# TSB_Rev1.net
KiCad netlist of a schematic drawn in EAGLE
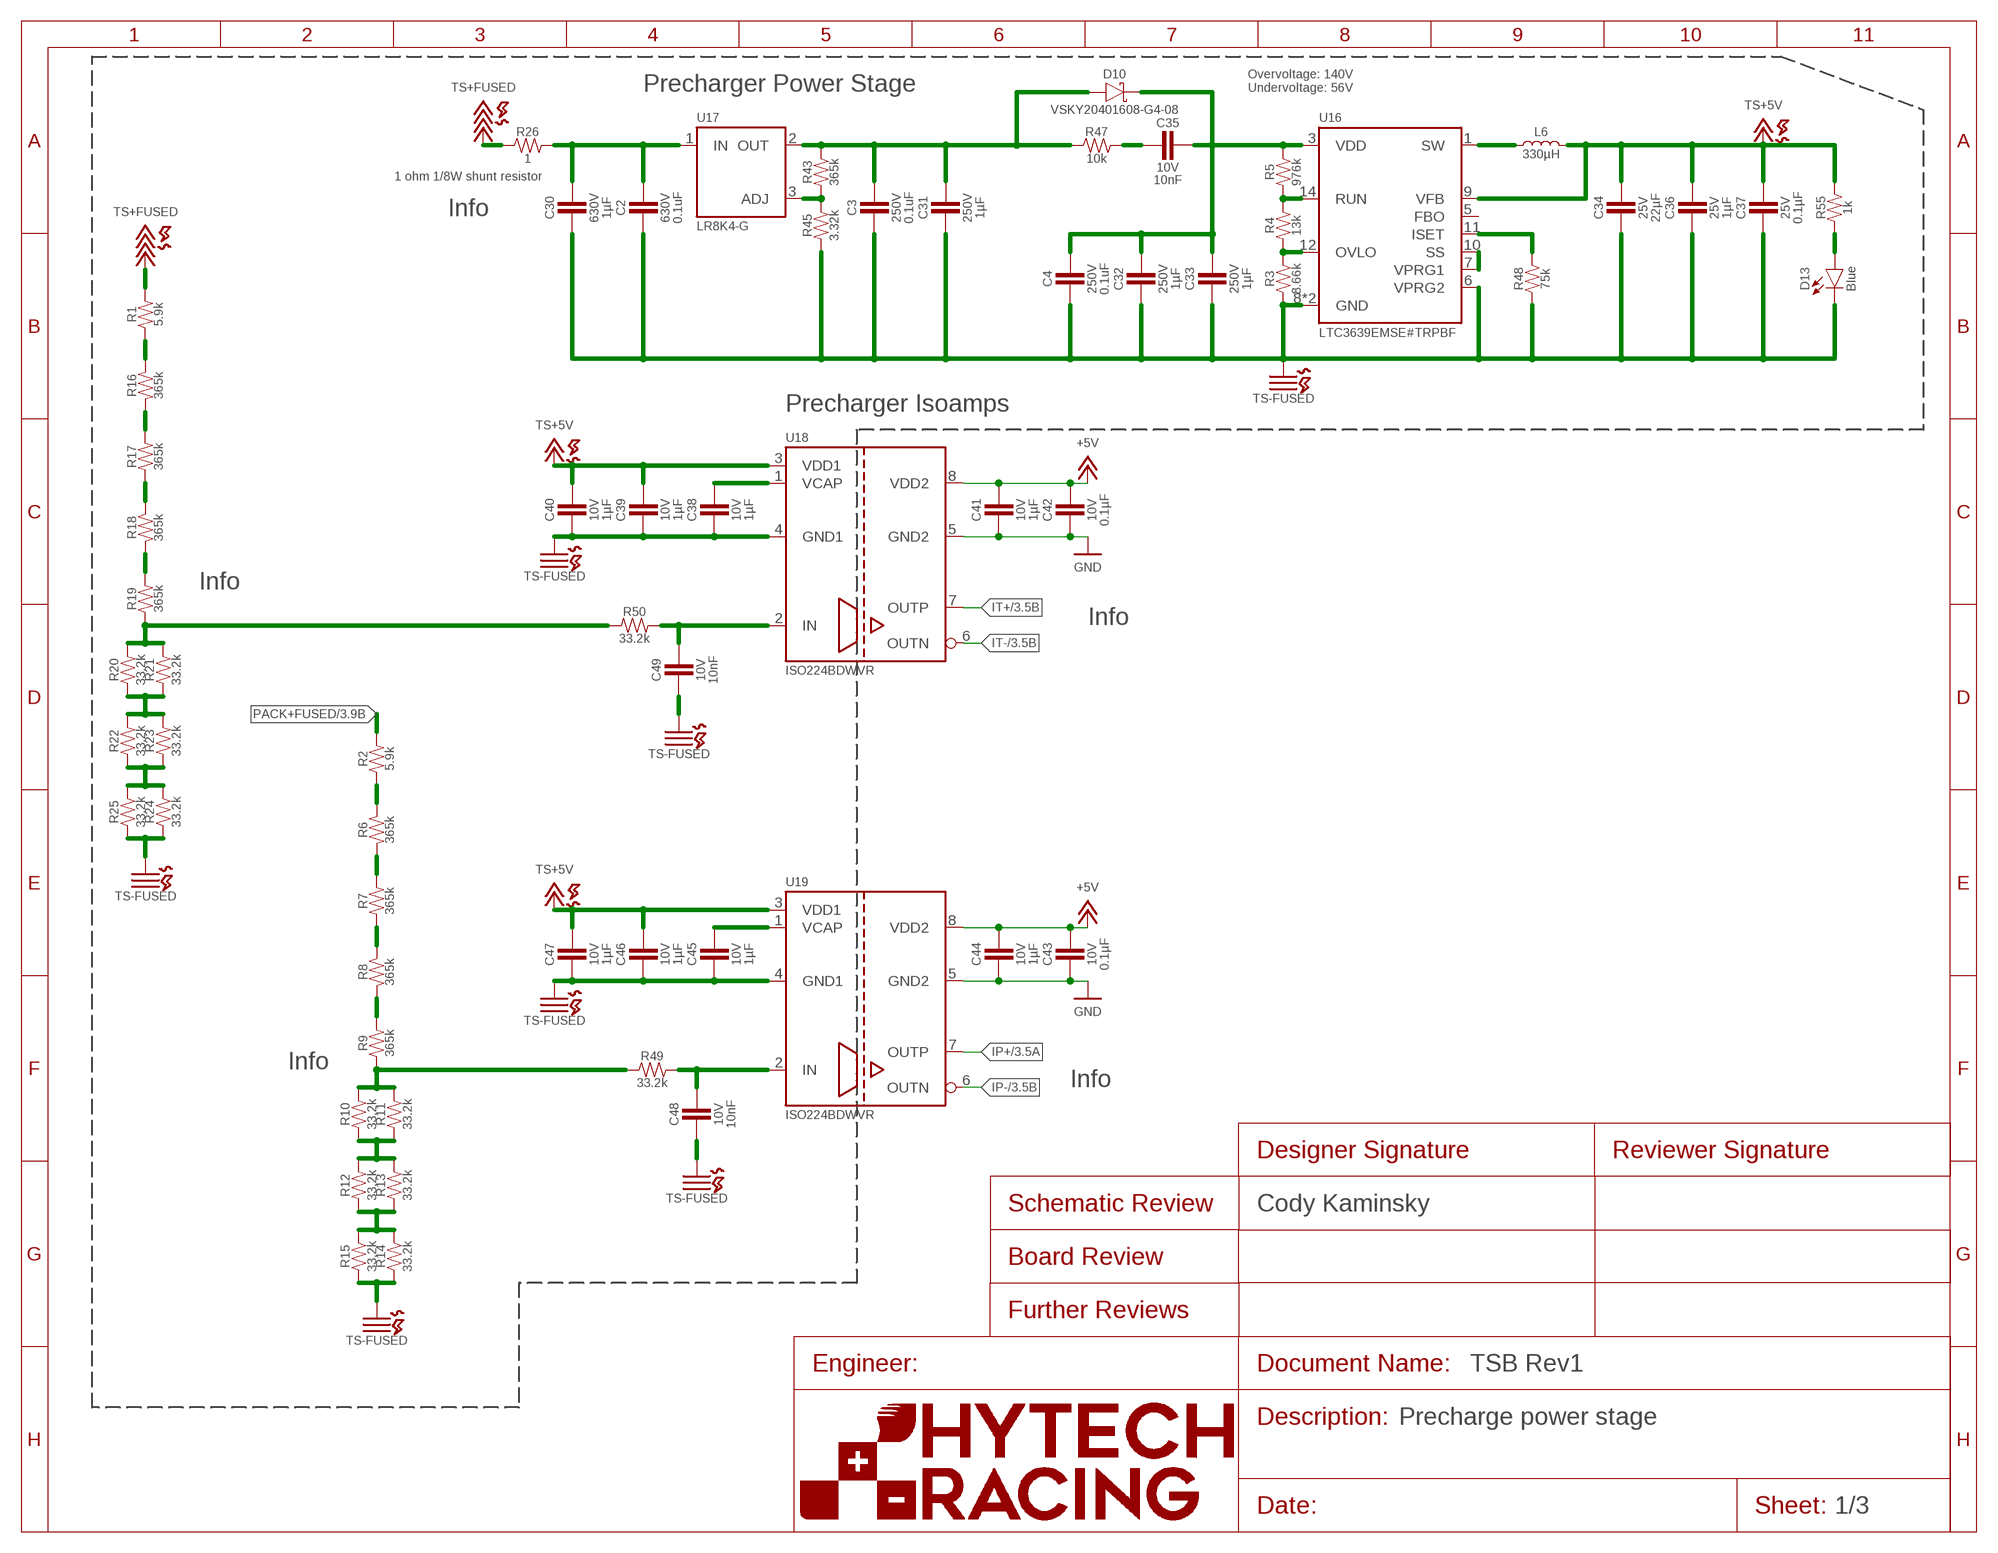
[diagram p0: schematic, sheet 1]
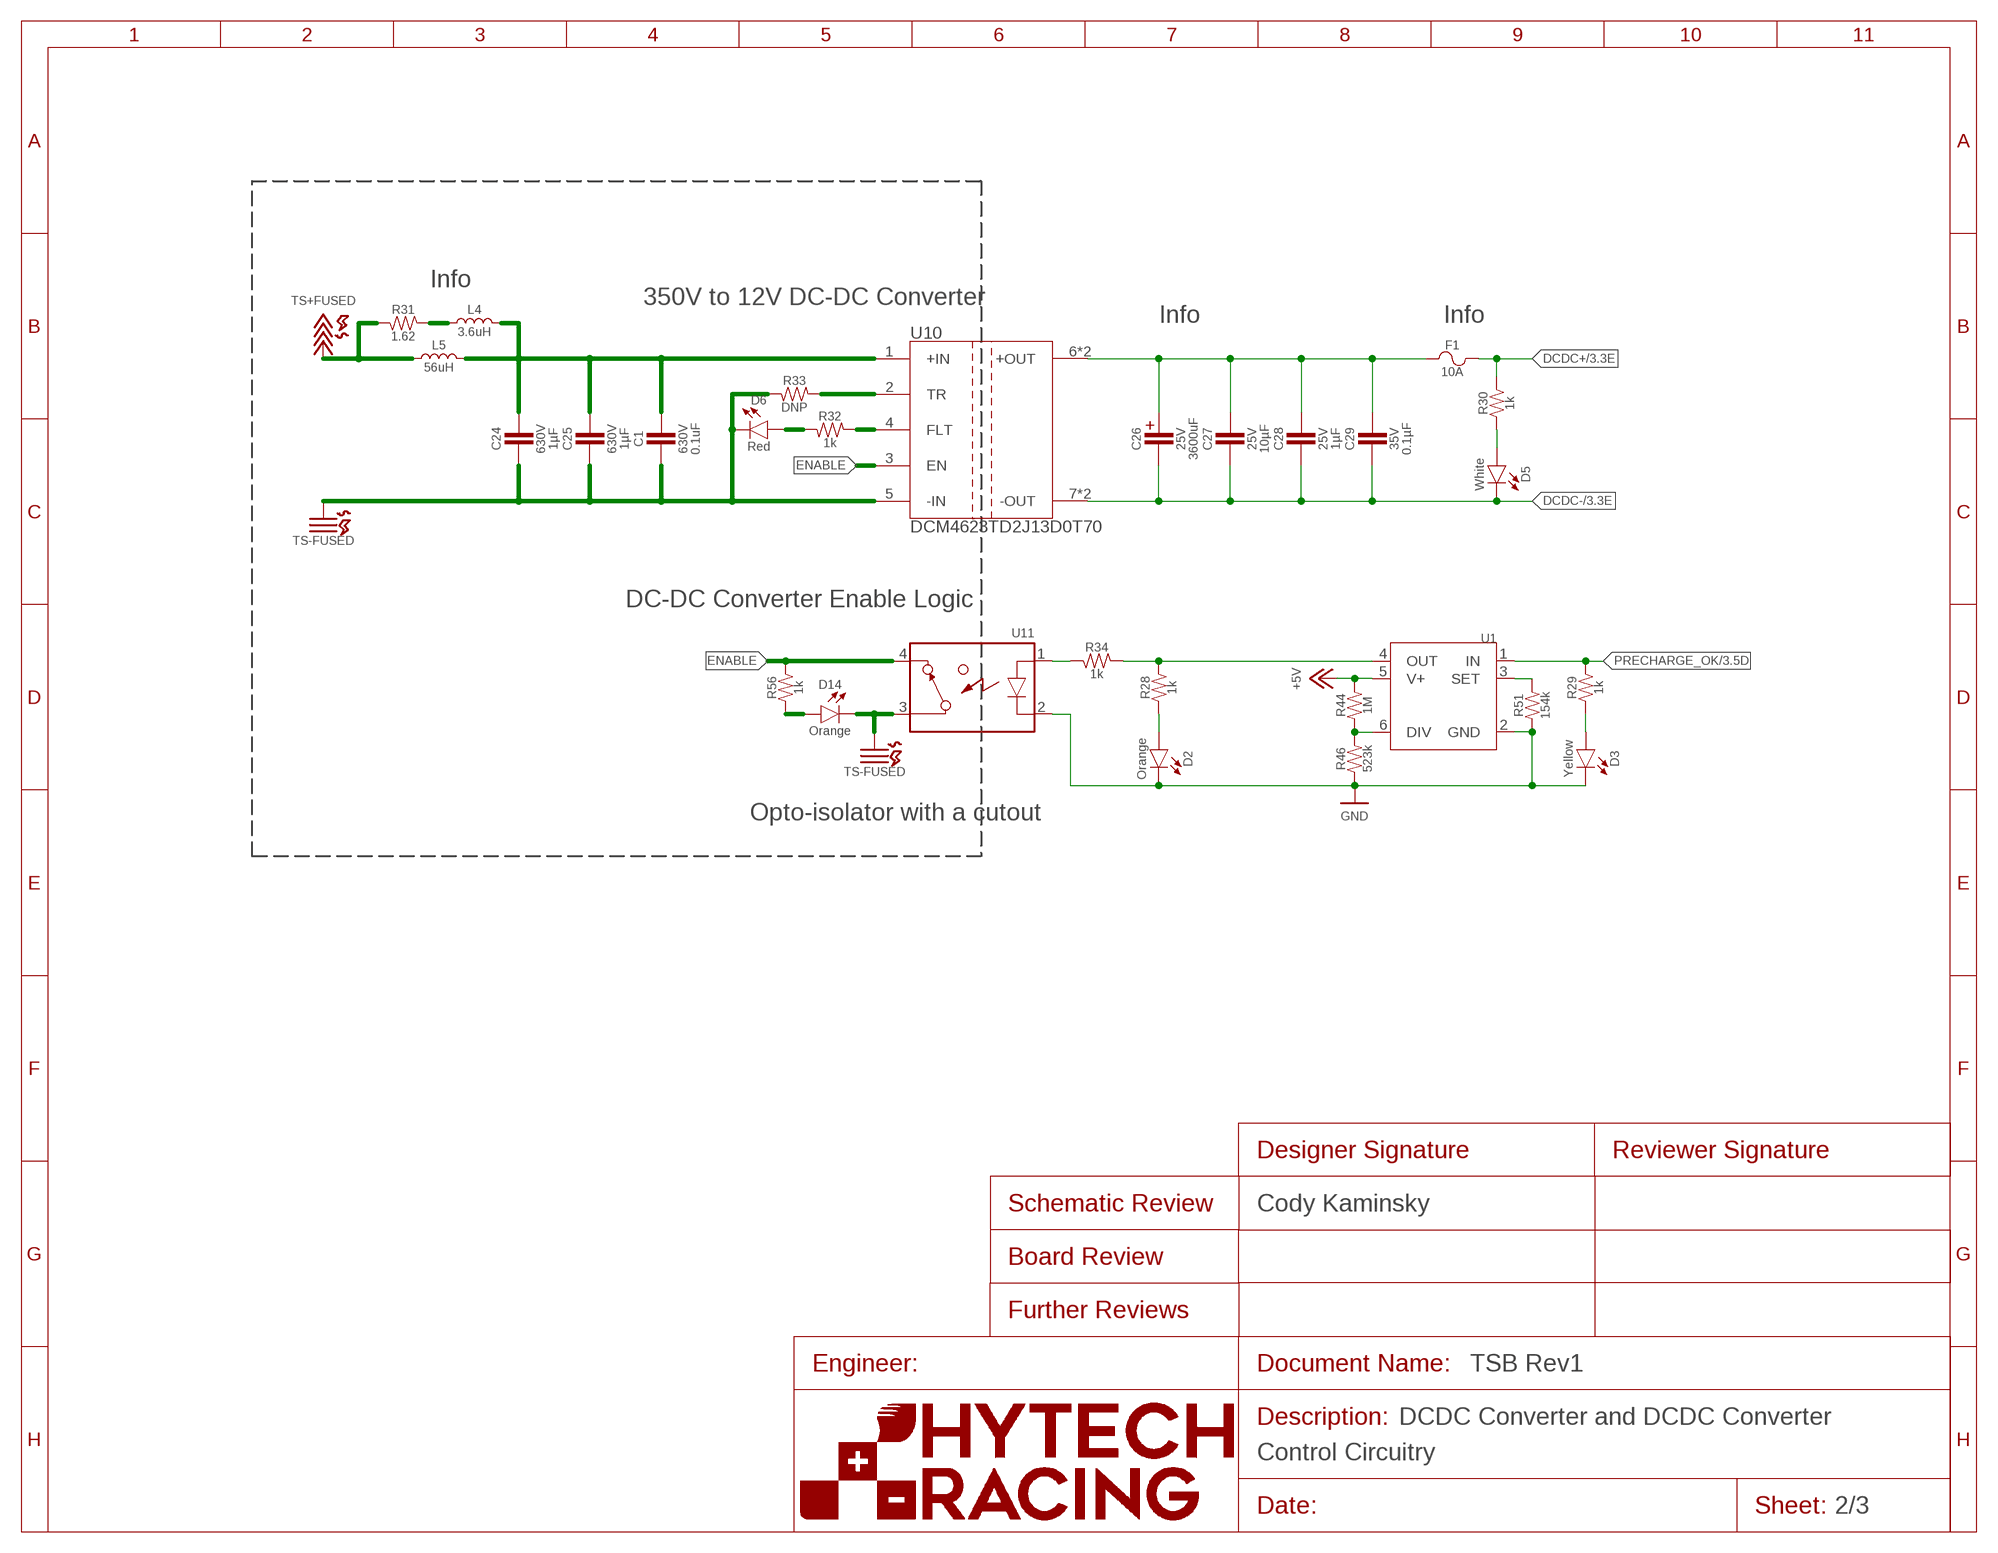
[diagram p1: schematic, sheet 2]
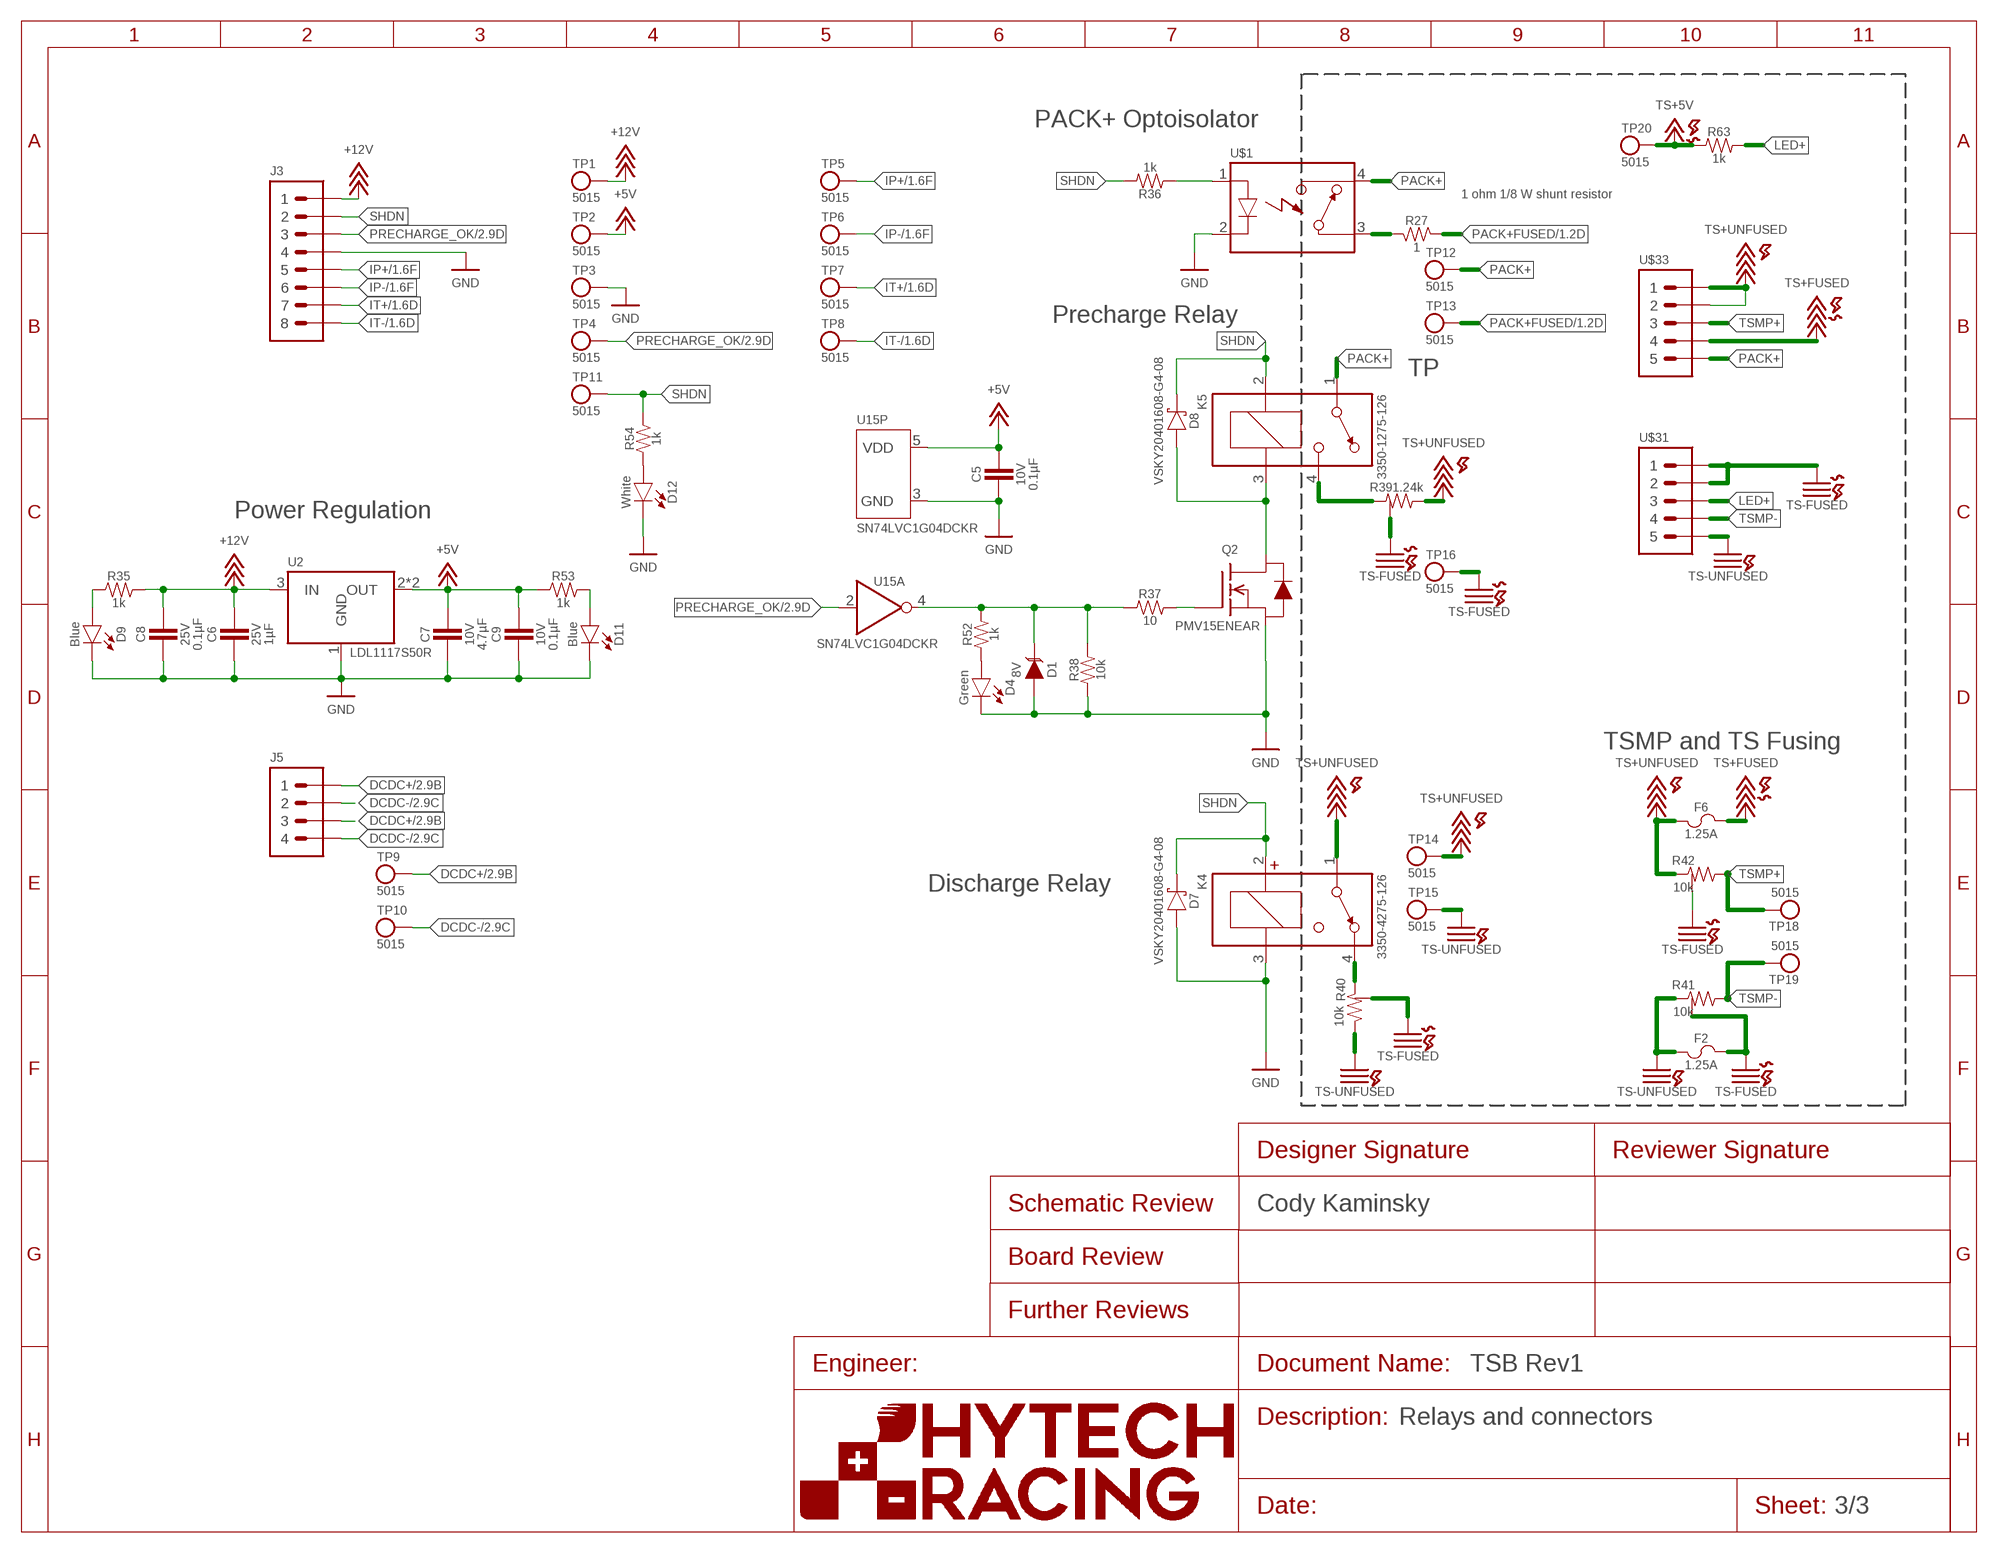
[diagram p2: schematic, sheet 3]

(export (version "E")
  (design (tool "Eeschema 10.0.6"))
  (components
    (comp (ref "C1")
      (value "CAPACITOR_2220_630V_0.1UF")
      (footprint "eagle-import:2220-CAP")
      (fields
        (field (name "CAPACITANCE") "0.1uF")
        (field (name "MANUFACTURER") "TDK Coporation")
        (field (name "MPN") "C5750CH2J104K280KC")
        (field (name "TOLERANCE") "10%")
        (field (name "VOLTAGE") "630V")
      )
      (libsource (lib "eagle-import") (part "CAPACITOR_?_2220630V_0.1UF"))
    )
    (comp (ref "C24")
      (value "CAPACITOR_2220_630V_1UF")
      (footprint "eagle-import:2220-CAP")
      (fields
        (field (name "CAPACITANCE") "1µF")
        (field (name "MANUFACTURER") "Knowles Syfer")
        (field (name "MPN") "2220Y6300105KXTWS2")
        (field (name "TOLERANCE") "10%")
        (field (name "VOLTAGE") "630V")
      )
      (libsource (lib "eagle-import") (part "CAPACITOR_?_2220630V_1UF"))
    )
    (comp (ref "C25")
      (value "CAPACITOR_2220_630V_1UF")
      (footprint "eagle-import:2220-CAP")
      (fields
        (field (name "CAPACITANCE") "1µF")
        (field (name "MANUFACTURER") "Knowles Syfer")
        (field (name "MPN") "2220Y6300105KXTWS2")
        (field (name "TOLERANCE") "10%")
        (field (name "VOLTAGE") "630V")
      )
      (libsource (lib "eagle-import") (part "CAPACITOR_?_2220630V_1UF"))
    )
    (comp (ref "C26")
      (value "CAPACITOR_POLAR__")
      (footprint "eagle-import:EKYC_MM")
      (fields
        (field (name "VOLTAGE") "25V")
        (field (name "CAPACITANCE") "3600uF")
        (field (name "MANUFACTURER") "United Chemi-con")
        (field (name "MPN") "EKYC250ELL362ML20S")
      )
      (libsource (lib "eagle-import") (part "CAPACITOR_POLAR_?_"))
    )
    (comp (ref "C27")
      (value "CAPACITOR_0603_25V_10UF")
      (footprint "eagle-import:0603-CAP")
      (fields
        (field (name "CAPACITANCE") "10µF")
        (field (name "MANUFACTURER") "Murata Electronics")
        (field (name "MPN") "GRM188R61E106MA73D")
        (field (name "TOLERANCE") "20%")
        (field (name "VOLTAGE") "25V")
      )
      (libsource (lib "eagle-import") (part "CAPACITOR_?_060325V_10UF"))
    )
    (comp (ref "C28")
      (value "CAPACITOR_0603_25V_1UF")
      (footprint "eagle-import:0603-CAP")
      (fields
        (field (name "CAPACITANCE") "1µF")
        (field (name "MANUFACTURER") "Samsung Electro-Mechanics")
        (field (name "MPN") "CL10B105KA8NNNC")
        (field (name "TOLERANCE") "10%")
        (field (name "VOLTAGE") "25V")
      )
      (libsource (lib "eagle-import") (part "CAPACITOR_?_060325V_1UF"))
    )
    (comp (ref "C29")
      (value "CAPACITOR_0603_35V_0.1UF")
      (footprint "eagle-import:0603-CAP")
      (fields
        (field (name "CAPACITANCE") "0.1µF")
        (field (name "MANUFACTURER") "Taiyo Yuden")
        (field (name "MPN") "GMK107B7104KAHT")
        (field (name "TOLERANCE") "10%")
        (field (name "VOLTAGE") "35V")
      )
      (libsource (lib "eagle-import") (part "CAPACITOR_?_060335V_0.1UF"))
    )
    (comp (ref "D2")
      (value "LED_0603_ORANGE")
      (footprint "eagle-import:0603-LED")
      (fields
        (field (name "COLOR") "Orange")
        (field (name "MANUFACTURER") "Kingbright")
        (field (name "MPN") "APT1608SECK")
      )
      (libsource (lib "eagle-import") (part "LED_?_0603ORANGE"))
    )
    (comp (ref "D3")
      (value "LED_0603_YELLOW")
      (footprint "eagle-import:0603-LED")
      (fields
        (field (name "COLOR") "Yellow")
        (field (name "MANUFACTURER") "Kingbright")
        (field (name "MPN") "APT1608SYCK/J3-PRV")
      )
      (libsource (lib "eagle-import") (part "LED_?_0603YELLOW"))
    )
    (comp (ref "D5")
      (value "LED_0603_WHITE")
      (footprint "eagle-import:0603-LED")
      (fields
        (field (name "COLOR") "White")
        (field (name "MANUFACTURER") "Bivar Inc.")
        (field (name "MPN") "SM0603UWC")
      )
      (libsource (lib "eagle-import") (part "LED_?_0603WHITE"))
    )
    (comp (ref "D6")
      (value "LED_0603_RED")
      (footprint "eagle-import:0603-LED")
      (fields
        (field (name "COLOR") "Red")
        (field (name "MANUFACTURER") "Kingbright")
        (field (name "MPN") "APT1608SECK/J3-PRV")
      )
      (libsource (lib "eagle-import") (part "LED_?_0603RED"))
    )
    (comp (ref "D14")
      (value "LED_0603_ORANGE")
      (footprint "eagle-import:0603-LED")
      (fields
        (field (name "COLOR") "Orange")
        (field (name "MANUFACTURER") "Kingbright")
        (field (name "MPN") "APT1608SECK")
      )
      (libsource (lib "eagle-import") (part "LED_?_0603ORANGE"))
    )
    (comp (ref "F1")
      (value "FUSE__")
      (footprint "eagle-import:MINI-BLADE_FUSE_HOLDER")
      (fields
        (field (name "CURRENT") "10A")
        (field (name "MANUFACTURER") "Littelfuse Inc.")
        (field (name "MPN") "0297010.WXNV")
        (field (name "VOLTAGE") "32V")
      )
      (libsource (lib "eagle-import") (part "FUSE_?_"))
    )
    (comp (ref "L4")
      (value "INDUCTOR_PA4334_")
      (footprint "eagle-import:PA4334")
      (fields (field (name "INDUCTANCE") "3.6uH") (field (name "MANUFACTURER") "Pulse Electonics Company"))
      (libsource (lib "eagle-import") (part "INDUCTOR_?_PA4334"))
    )
    (comp (ref "L5")
      (value "INDUCTOR_WELMHI_")
      (footprint "eagle-import:WE-LMHI")
      (fields (field (name "INDUCTANCE") "56uH"))
      (libsource (lib "eagle-import") (part "INDUCTOR_?_WELMHI"))
    )
    (comp (ref "R28")
      (value "RESISTOR_0603_1K")
      (footprint "eagle-import:0603-RES")
      (fields
        (field (name "MANUFACTURER") "Yageo")
        (field (name "MPN") "RC0603FR-071KL")
        (field (name "POWER") "0.1W")
        (field (name "RESISTANCE") "1k")
      )
      (libsource (lib "eagle-import") (part "RESISTOR_?_06031K"))
    )
    (comp (ref "R29")
      (value "RESISTOR_0603_1K")
      (footprint "eagle-import:0603-RES")
      (fields
        (field (name "MANUFACTURER") "Yageo")
        (field (name "MPN") "RC0603FR-071KL")
        (field (name "POWER") "0.1W")
        (field (name "RESISTANCE") "1k")
      )
      (libsource (lib "eagle-import") (part "RESISTOR_?_06031K"))
    )
    (comp (ref "R30")
      (value "RESISTOR_0603_1K")
      (footprint "eagle-import:0603-RES")
      (fields
        (field (name "MANUFACTURER") "Yageo")
        (field (name "MPN") "RC0603FR-071KL")
        (field (name "POWER") "0.1W")
        (field (name "RESISTANCE") "1k")
      )
      (libsource (lib "eagle-import") (part "RESISTOR_?_06031K"))
    )
    (comp (ref "R31")
      (value "RESISTOR_0603_1.62")
      (footprint "eagle-import:0603-RES")
      (fields
        (field (name "MANUFACTURER") "TE Conductivity Passive Product")
        (field (name "MPN") "CPF0603B1R62E1")
        (field (name "POWER") "0.1W")
        (field (name "RESISTANCE") "1.62")
      )
      (libsource (lib "eagle-import") (part "RESISTOR_?_06031.62"))
    )
    (comp (ref "R32")
      (value "RESISTOR_0603_1K")
      (footprint "eagle-import:0603-RES")
      (fields
        (field (name "MANUFACTURER") "Yageo")
        (field (name "MPN") "RC0603FR-071KL")
        (field (name "POWER") "0.1W")
        (field (name "RESISTANCE") "1k")
      )
      (libsource (lib "eagle-import") (part "RESISTOR_?_06031K"))
    )
    (comp (ref "R33")
      (value "RESISTOR_0603_DNP")
      (footprint "eagle-import:0603-RES")
      (fields (field (name "RESISTANCE") "DNP"))
      (libsource (lib "eagle-import") (part "RESISTOR_?_0603DNP"))
    )
    (comp (ref "R34")
      (value "RESISTOR_0603_1K")
      (footprint "eagle-import:0603-RES")
      (fields
        (field (name "MANUFACTURER") "Yageo")
        (field (name "MPN") "RC0603FR-071KL")
        (field (name "POWER") "0.1W")
        (field (name "RESISTANCE") "1k")
      )
      (libsource (lib "eagle-import") (part "RESISTOR_?_06031K"))
    )
    (comp (ref "R44")
      (value "RESISTOR_0805_1M")
      (footprint "eagle-import:0805-RES")
      (fields
        (field (name "MANUFACTURER") "Panasonic Electronic Components")
        (field (name "MPN") "ERJ-PB6B1004V")
        (field (name "POWER") "0.25W")
        (field (name "RESISTANCE") "1M")
      )
      (libsource (lib "eagle-import") (part "RESISTOR_?_08051M"))
    )
    (comp (ref "R46")
      (value "RESISTOR_0805_523K")
      (footprint "eagle-import:0805-RES")
      (fields
        (field (name "MANUFACTURER") "Panasonic Electronic Components")
        (field (name "MPN") "ERJ-PB6B5233V")
        (field (name "POWER") "0.25W")
        (field (name "RESISTANCE") "523k")
      )
      (libsource (lib "eagle-import") (part "RESISTOR_?_0805523K"))
    )
    (comp (ref "R51")
      (value "RESISTOR_0603_154K")
      (footprint "eagle-import:0603-RES")
      (fields
        (field (name "MANUFACTURER") "Panasonic Electronic Components")
        (field (name "MPN") "ERA-3AEB1543V")
        (field (name "POWER") "0.1W")
        (field (name "RESISTANCE") "154k")
      )
      (libsource (lib "eagle-import") (part "RESISTOR_?_0603154K"))
    )
    (comp (ref "R56")
      (value "RESISTOR_0603_1K")
      (footprint "eagle-import:0603-RES")
      (fields
        (field (name "MANUFACTURER") "Yageo")
        (field (name "MPN") "RC0603FR-071KL")
        (field (name "POWER") "0.1W")
        (field (name "RESISTANCE") "1k")
      )
      (libsource (lib "eagle-import") (part "RESISTOR_?_06031K"))
    )
    (comp (ref "U1")
      (value "LTC6994_1")
      (footprint "eagle-import:SOT-23-6")
      (libsource (lib "eagle-import") (part "LTC6994_1"))
    )
    (comp (ref "U10")
      (value "DCM4623TD2J13D0T70")
      (footprint "eagle-import:DCM4623")
      (libsource (lib "eagle-import") (part "DCM4623TD2J13D0T70"))
    )
    (comp (ref "U11")
      (value "RELAY_SOLIDSTATE_NC_AG")
      (footprint "eagle-import:DIP-4_AIRGAP")
      (libsource (lib "eagle-import") (part "RELAY_SOLIDSTATE_NC_?AG"))
    )
    (comp (ref "C5")
      (value "CAPACITOR_0603_10V_0.1UF")
      (footprint "eagle-import:0603-CAP")
      (fields
        (field (name "CAPACITANCE") "0.1µF")
        (field (name "MANUFACTURER") "Vishay Vitramon")
        (field (name "MPN") "VJ0603Y104JXQPW1BC")
        (field (name "TOLERANCE") "5%")
        (field (name "VOLTAGE") "10V")
      )
      (libsource (lib "eagle-import") (part "CAPACITOR_?_060310V_0.1UF"))
    )
    (comp (ref "C6")
      (value "CAPACITOR_0603_25V_1UF")
      (footprint "eagle-import:0603-CAP")
      (fields
        (field (name "CAPACITANCE") "1µF")
        (field (name "MANUFACTURER") "Samsung Electro-Mechanics")
        (field (name "MPN") "CL10B105KA8NNNC")
        (field (name "TOLERANCE") "10%")
        (field (name "VOLTAGE") "25V")
      )
      (libsource (lib "eagle-import") (part "CAPACITOR_?_060325V_1UF"))
    )
    (comp (ref "C7")
      (value "CAPACITOR_0603_10V_4.7UF")
      (footprint "eagle-import:0603-CAP")
      (fields
        (field (name "CAPACITANCE") "4.7µF")
        (field (name "MANUFACTURER") "Samsung Electro-Mechanics")
        (field (name "MPN") "CL10A475KP8NNNC")
        (field (name "TOLERANCE") "10%")
        (field (name "VOLTAGE") "10V")
      )
      (libsource (lib "eagle-import") (part "CAPACITOR_?_060310V_4.7UF"))
    )
    (comp (ref "C8")
      (value "CAPACITOR_0603_25V_0.1UF")
      (footprint "eagle-import:0603-CAP")
      (fields
        (field (name "CAPACITANCE") "0.1µF")
        (field (name "MANUFACTURER") "Samsung Electro-Mechanics")
        (field (name "MPN") "CL10B104KA8NNNC")
        (field (name "TOLERANCE") "10%")
        (field (name "VOLTAGE") "25V")
      )
      (libsource (lib "eagle-import") (part "CAPACITOR_?_060325V_0.1UF"))
    )
    (comp (ref "C9")
      (value "CAPACITOR_0603_10V_0.1UF")
      (footprint "eagle-import:0603-CAP")
      (fields
        (field (name "CAPACITANCE") "0.1µF")
        (field (name "MANUFACTURER") "Vishay Vitramon")
        (field (name "MPN") "VJ0603Y104JXQPW1BC")
        (field (name "TOLERANCE") "5%")
        (field (name "VOLTAGE") "10V")
      )
      (libsource (lib "eagle-import") (part "CAPACITOR_?_060310V_0.1UF"))
    )
    (comp (ref "D1")
      (value "TVS_8V")
      (footprint "eagle-import:SOT-23")
      (fields
        (field (name "MANUFACTURER") "Vishay General Semiconductor - Diodes Division")
        (field (name "MPN") "GSOT08-E3-08")
        (field (name "VOLTAGE") "8V")
      )
      (libsource (lib "eagle-import") (part "TVS_8V"))
    )
    (comp (ref "D4")
      (value "LED_0603_GREEN")
      (footprint "eagle-import:0603-LED")
      (fields
        (field (name "COLOR") "Green")
        (field (name "MANUFACTURER") "Kingbright")
        (field (name "MPN") "APT1608ZGCK")
      )
      (libsource (lib "eagle-import") (part "LED_?_0603GREEN"))
    )
    (comp (ref "D7")
      (value "SCHOTTKY")
      (footprint "eagle-import:CLP1608-2L")
      (fields
        (field (name "MPN") "VSKY20401608-G4-08")
        (field (name "MANUFACTURER") "Vishay General Semiconductor - Diodes Division")
      )
      (libsource (lib "eagle-import") (part "SCHOTTKY"))
    )
    (comp (ref "D8")
      (value "SCHOTTKY")
      (footprint "eagle-import:CLP1608-2L")
      (fields
        (field (name "MPN") "VSKY20401608-G4-08")
        (field (name "MANUFACTURER") "Vishay General Semiconductor - Diodes Division")
      )
      (libsource (lib "eagle-import") (part "SCHOTTKY"))
    )
    (comp (ref "D9")
      (value "LED_0603_BLUE")
      (footprint "eagle-import:0603-LED")
      (fields
        (field (name "COLOR") "Blue")
        (field (name "MANUFACTURER") "Kingbright")
        (field (name "MPN") "APT1608VBC/D")
      )
      (libsource (lib "eagle-import") (part "LED_?_0603BLUE"))
    )
    (comp (ref "D11")
      (value "LED_0603_BLUE")
      (footprint "eagle-import:0603-LED")
      (fields
        (field (name "COLOR") "Blue")
        (field (name "MANUFACTURER") "Kingbright")
        (field (name "MPN") "APT1608VBC/D")
      )
      (libsource (lib "eagle-import") (part "LED_?_0603BLUE"))
    )
    (comp (ref "D12")
      (value "LED_0603_WHITE")
      (footprint "eagle-import:0603-LED")
      (fields
        (field (name "COLOR") "White")
        (field (name "MANUFACTURER") "Bivar Inc.")
        (field (name "MPN") "SM0603UWC")
      )
      (libsource (lib "eagle-import") (part "LED_?_0603WHITE"))
    )
    (comp (ref "F2")
      (value "FUSE_0885_1.25")
      (footprint "eagle-import:0885")
      (fields
        (field (name "CURRENT") "1.25A")
        (field (name "MANUFACTURER") "Littelfuse Inc.")
        (field (name "MPN") "08851.25DR")
        (field (name "VOLTAGE") "500V")
      )
      (libsource (lib "eagle-import") (part "FUSE_?_08851.25"))
    )
    (comp (ref "F6")
      (value "FUSE_0885_1.25")
      (footprint "eagle-import:0885")
      (fields
        (field (name "CURRENT") "1.25A")
        (field (name "MANUFACTURER") "Littelfuse Inc.")
        (field (name "MPN") "08851.25DR")
        (field (name "VOLTAGE") "500V")
      )
      (libsource (lib "eagle-import") (part "FUSE_?_08851.25"))
    )
    (comp (ref "J3")
      (value "CONNECTOR-8_MF_T_V_")
      (footprint "eagle-import:MOLEX_MICROFIT_PTH_VERTICAL_08_DUAL")
      (libsource (lib "eagle-import") (part "CONNECTOR-8_?_MF_T_V"))
    )
    (comp (ref "J5")
      (value "CONNECTOR-4__")
      (footprint "eagle-import:MOLEX_MICROFIT_PTH_VERTICAL_04_DUAL")
      (libsource (lib "eagle-import") (part "CONNECTOR-4_?_"))
    )
    (comp (ref "K4")
      (value "RELAY_SPST_NC_POLARIZED_3550_12")
      (footprint "eagle-import:335X")
      (fields (field (name "MANUFACTURER") "Comus International") (field (name "MPN") "3350-4275-126"))
      (libsource (lib "eagle-import") (part "RELAY_SPST_NC_POLARIZED_?3550_12"))
    )
    (comp (ref "K5")
      (value "RELAY_SPST_NO_3550_12")
      (footprint "eagle-import:335X")
      (fields (field (name "MANUFACTURER") "Comus International") (field (name "MPN") "3350-1275-126"))
      (libsource (lib "eagle-import") (part "RELAY_SPST_NO_?3550_12"))
    )
    (comp (ref "Q2")
      (value "TRANSISTOR_N_MOS__PMV15ENEA")
      (footprint "eagle-import:SOT-23")
      (fields (field (name "MANUFACTURER") "Nexperia USA Inc.") (field (name "MPN") "PMV15ENEAR"))
      (libsource (lib "eagle-import") (part "TRANSISTOR_N_MOS_?_PMV15ENEA"))
    )
    (comp (ref "R27")
      (value "RESISTOR_0805_1")
      (footprint "eagle-import:0805-RES")
      (fields
        (field (name "MANUFACTURER") "Panasonic Electronic Components")
        (field (name "MPN") "ERJ-6RQF1R0V")
        (field (name "POWER") "0.125W")
        (field (name "RESISTANCE") "1")
      )
      (libsource (lib "eagle-import") (part "RESISTOR_?_08051"))
    )
    (comp (ref "R35")
      (value "RESISTOR_0603_1K")
      (footprint "eagle-import:0603-RES")
      (fields
        (field (name "MANUFACTURER") "Yageo")
        (field (name "MPN") "RC0603FR-071KL")
        (field (name "POWER") "0.1W")
        (field (name "RESISTANCE") "1k")
      )
      (libsource (lib "eagle-import") (part "RESISTOR_?_06031K"))
    )
    (comp (ref "R36")
      (value "RESISTOR_0603_1K")
      (footprint "eagle-import:0603-RES")
      (fields
        (field (name "MANUFACTURER") "Yageo")
        (field (name "MPN") "RC0603FR-071KL")
        (field (name "POWER") "0.1W")
        (field (name "RESISTANCE") "1k")
      )
      (libsource (lib "eagle-import") (part "RESISTOR_?_06031K"))
    )
    (comp (ref "R37")
      (value "RESISTOR_0603_10")
      (footprint "eagle-import:0603-RES")
      (fields
        (field (name "MANUFACTURER") "Yageo")
        (field (name "MPN") "RC0603FR-0710RL")
        (field (name "POWER") "0.1W")
        (field (name "RESISTANCE") "10")
      )
      (libsource (lib "eagle-import") (part "RESISTOR_?_060310"))
    )
    (comp (ref "R38")
      (value "RESISTOR_0603_10K")
      (footprint "eagle-import:0603-RES")
      (fields
        (field (name "MANUFACTURER") "Yageo")
        (field (name "MPN") "RC0603FR-0710KL")
        (field (name "POWER") "0.1W")
        (field (name "RESISTANCE") "10k")
      )
      (libsource (lib "eagle-import") (part "RESISTOR_?_060310K"))
    )
    (comp (ref "R39")
      (value "RESISTOR_GND_1.24K")
      (footprint "eagle-import:B20")
      (fields (field (name "RESISTANCE") "1.24k"))
      (libsource (lib "eagle-import") (part "RESISTOR_GND_1.24K"))
    )
    (comp (ref "R40")
      (value "RESISTOR_GND_10K")
      (footprint "eagle-import:B20")
      (fields (field (name "RESISTANCE") "10k"))
      (libsource (lib "eagle-import") (part "RESISTOR_GND_10K"))
    )
    (comp (ref "R41")
      (value "RESISTOR_GND_10K")
      (footprint "eagle-import:B20")
      (fields (field (name "RESISTANCE") "10k"))
      (libsource (lib "eagle-import") (part "RESISTOR_GND_10K"))
    )
    (comp (ref "R42")
      (value "RESISTOR_GND_10K")
      (footprint "eagle-import:B20")
      (fields (field (name "RESISTANCE") "10k"))
      (libsource (lib "eagle-import") (part "RESISTOR_GND_10K"))
    )
    (comp (ref "R52")
      (value "RESISTOR_0603_1K")
      (footprint "eagle-import:0603-RES")
      (fields
        (field (name "MANUFACTURER") "Yageo")
        (field (name "MPN") "RC0603FR-071KL")
        (field (name "POWER") "0.1W")
        (field (name "RESISTANCE") "1k")
      )
      (libsource (lib "eagle-import") (part "RESISTOR_?_06031K"))
    )
    (comp (ref "R53")
      (value "RESISTOR_0603_1K")
      (footprint "eagle-import:0603-RES")
      (fields
        (field (name "MANUFACTURER") "Yageo")
        (field (name "MPN") "RC0603FR-071KL")
        (field (name "POWER") "0.1W")
        (field (name "RESISTANCE") "1k")
      )
      (libsource (lib "eagle-import") (part "RESISTOR_?_06031K"))
    )
    (comp (ref "R54")
      (value "RESISTOR_0603_1K")
      (footprint "eagle-import:0603-RES")
      (fields
        (field (name "MANUFACTURER") "Yageo")
        (field (name "MPN") "RC0603FR-071KL")
        (field (name "POWER") "0.1W")
        (field (name "RESISTANCE") "1k")
      )
      (libsource (lib "eagle-import") (part "RESISTOR_?_06031K"))
    )
    (comp (ref "R63")
      (value "RESISTOR_0603_1K")
      (footprint "eagle-import:0603-RES")
      (fields
        (field (name "MANUFACTURER") "Yageo")
        (field (name "MPN") "RC0603FR-071KL")
        (field (name "POWER") "0.1W")
        (field (name "RESISTANCE") "1k")
      )
      (libsource (lib "eagle-import") (part "RESISTOR_?_06031K"))
    )
    (comp (ref "TP1")
      (value "TEST_POINT")
      (footprint "eagle-import:MICRO_MINIATURE")
      (fields (field (name "MPN") "5015") (field (name "MANUFACTURER") "Keystone Electronics"))
      (libsource (lib "eagle-import") (part "TEST_POINT"))
    )
    (comp (ref "TP2")
      (value "TEST_POINT")
      (footprint "eagle-import:MICRO_MINIATURE")
      (fields (field (name "MPN") "5015") (field (name "MANUFACTURER") "Keystone Electronics"))
      (libsource (lib "eagle-import") (part "TEST_POINT"))
    )
    (comp (ref "TP3")
      (value "TEST_POINT")
      (footprint "eagle-import:MICRO_MINIATURE")
      (fields (field (name "MPN") "5015") (field (name "MANUFACTURER") "Keystone Electronics"))
      (libsource (lib "eagle-import") (part "TEST_POINT"))
    )
    (comp (ref "TP4")
      (value "TEST_POINT")
      (footprint "eagle-import:MICRO_MINIATURE")
      (fields (field (name "MPN") "5015") (field (name "MANUFACTURER") "Keystone Electronics"))
      (libsource (lib "eagle-import") (part "TEST_POINT"))
    )
    (comp (ref "TP5")
      (value "TEST_POINT")
      (footprint "eagle-import:MICRO_MINIATURE")
      (fields (field (name "MPN") "5015") (field (name "MANUFACTURER") "Keystone Electronics"))
      (libsource (lib "eagle-import") (part "TEST_POINT"))
    )
    (comp (ref "TP6")
      (value "TEST_POINT")
      (footprint "eagle-import:MICRO_MINIATURE")
      (fields (field (name "MPN") "5015") (field (name "MANUFACTURER") "Keystone Electronics"))
      (libsource (lib "eagle-import") (part "TEST_POINT"))
    )
    (comp (ref "TP7")
      (value "TEST_POINT")
      (footprint "eagle-import:MICRO_MINIATURE")
      (fields (field (name "MPN") "5015") (field (name "MANUFACTURER") "Keystone Electronics"))
      (libsource (lib "eagle-import") (part "TEST_POINT"))
    )
    (comp (ref "TP8")
      (value "TEST_POINT")
      (footprint "eagle-import:MICRO_MINIATURE")
      (fields (field (name "MPN") "5015") (field (name "MANUFACTURER") "Keystone Electronics"))
      (libsource (lib "eagle-import") (part "TEST_POINT"))
    )
    (comp (ref "TP9")
      (value "TEST_POINT")
      (footprint "eagle-import:MICRO_MINIATURE")
      (fields (field (name "MPN") "5015") (field (name "MANUFACTURER") "Keystone Electronics"))
      (libsource (lib "eagle-import") (part "TEST_POINT"))
    )
    (comp (ref "TP10")
      (value "TEST_POINT")
      (footprint "eagle-import:MICRO_MINIATURE")
      (fields (field (name "MPN") "5015") (field (name "MANUFACTURER") "Keystone Electronics"))
      (libsource (lib "eagle-import") (part "TEST_POINT"))
    )
    (comp (ref "TP11")
      (value "TEST_POINT")
      (footprint "eagle-import:MICRO_MINIATURE")
      (fields (field (name "MPN") "5015") (field (name "MANUFACTURER") "Keystone Electronics"))
      (libsource (lib "eagle-import") (part "TEST_POINT"))
    )
    (comp (ref "TP12")
      (value "TEST_POINT")
      (footprint "eagle-import:MICRO_MINIATURE")
      (fields (field (name "MPN") "5015") (field (name "MANUFACTURER") "Keystone Electronics"))
      (libsource (lib "eagle-import") (part "TEST_POINT"))
    )
    (comp (ref "TP13")
      (value "TEST_POINT")
      (footprint "eagle-import:MICRO_MINIATURE")
      (fields (field (name "MPN") "5015") (field (name "MANUFACTURER") "Keystone Electronics"))
      (libsource (lib "eagle-import") (part "TEST_POINT"))
    )
    (comp (ref "TP14")
      (value "TEST_POINT")
      (footprint "eagle-import:MICRO_MINIATURE")
      (fields (field (name "MPN") "5015") (field (name "MANUFACTURER") "Keystone Electronics"))
      (libsource (lib "eagle-import") (part "TEST_POINT"))
    )
    (comp (ref "TP15")
      (value "TEST_POINT")
      (footprint "eagle-import:MICRO_MINIATURE")
      (fields (field (name "MPN") "5015") (field (name "MANUFACTURER") "Keystone Electronics"))
      (libsource (lib "eagle-import") (part "TEST_POINT"))
    )
    (comp (ref "TP16")
      (value "TEST_POINT")
      (footprint "eagle-import:MICRO_MINIATURE")
      (fields (field (name "MPN") "5015") (field (name "MANUFACTURER") "Keystone Electronics"))
      (libsource (lib "eagle-import") (part "TEST_POINT"))
    )
    (comp (ref "TP18")
      (value "TEST_POINT")
      (footprint "eagle-import:MICRO_MINIATURE")
      (fields (field (name "MPN") "5015") (field (name "MANUFACTURER") "Keystone Electronics"))
      (libsource (lib "eagle-import") (part "TEST_POINT"))
    )
    (comp (ref "TP19")
      (value "TEST_POINT")
      (footprint "eagle-import:MICRO_MINIATURE")
      (fields (field (name "MPN") "5015") (field (name "MANUFACTURER") "Keystone Electronics"))
      (libsource (lib "eagle-import") (part "TEST_POINT"))
    )
    (comp (ref "TP20")
      (value "TEST_POINT")
      (footprint "eagle-import:MICRO_MINIATURE")
      (fields (field (name "MPN") "5015") (field (name "MANUFACTURER") "Keystone Electronics"))
      (libsource (lib "eagle-import") (part "TEST_POINT"))
    )
    (comp (ref "U$1")
      (value "RELAY_SOLIDSTATE_NO_AG")
      (footprint "eagle-import:DIP-4_AIRGAP")
      (libsource (lib "eagle-import") (part "RELAY_SOLIDSTATE_NO_?AG"))
    )
    (comp (ref "U$31")
      (value "CONNECTOR-5_6_SPACED_")
      (footprint "eagle-import:MOLEX_MICROFIT_PTH_VERTICAL_06_SINGLE_SPACED")
      (libsource (lib "eagle-import") (part "CONNECTOR-5_?_6_SPACED"))
    )
    (comp (ref "U$33")
      (value "CONNECTOR-5_7_SPACED_")
      (footprint "eagle-import:MOLEX_MICROFIT_PTH_VERTICAL_07_DUAL_SPACED")
      (libsource (lib "eagle-import") (part "CONNECTOR-5_?_7_SPACED"))
    )
    (comp (ref "U2")
      (value "VOLTAGE_REGULATOR_SOT223_5V")
      (footprint "eagle-import:SOT223")
      (fields (field (name "MANUFACTURER") "STMicroelectronics") (field (name "MPN") "LDL1117S50R"))
      (libsource (lib "eagle-import") (part "VOLTAGE_REGULATOR_?_SOT2235V"))
    )
    (comp (ref "U15")
      (value "LOGICGATE_INVERTER_DCKR")
      (footprint "eagle-import:SC-70-5")
      (fields (field (name "MANUFACTURER") "Texas Instruments") (field (name "MPN") "SN74LVC1G04DCKR"))
      (libsource (lib "eagle-import") (part "LOGICGATE_INVERTER_DCKR"))
    )
    (comp (ref "C2")
      (value "CAPACITOR_2220_630V_0.1UF")
      (footprint "eagle-import:2220-CAP")
      (fields
        (field (name "CAPACITANCE") "0.1uF")
        (field (name "MANUFACTURER") "TDK Coporation")
        (field (name "MPN") "C5750CH2J104K280KC")
        (field (name "TOLERANCE") "10%")
        (field (name "VOLTAGE") "630V")
      )
      (libsource (lib "eagle-import") (part "CAPACITOR_?_2220630V_0.1UF"))
    )
    (comp (ref "C3")
      (value "CAPACITOR_1206_250V_0.1UF")
      (footprint "eagle-import:1206-CAP")
      (fields
        (field (name "CAPACITANCE") "0.1uF")
        (field (name "MANUFACTURER") "TDK Corporation")
        (field (name "MPN") "C3216X7R2E104K160AM")
        (field (name "TOLERANCE") "10%")
        (field (name "VOLTAGE") "250V")
      )
      (libsource (lib "eagle-import") (part "CAPACITOR_?_1206250V_0.1UF"))
    )
    (comp (ref "C4")
      (value "CAPACITOR_1206_250V_0.1UF")
      (footprint "eagle-import:1206-CAP")
      (fields
        (field (name "CAPACITANCE") "0.1uF")
        (field (name "MANUFACTURER") "TDK Corporation")
        (field (name "MPN") "C3216X7R2E104K160AM")
        (field (name "TOLERANCE") "10%")
        (field (name "VOLTAGE") "250V")
      )
      (libsource (lib "eagle-import") (part "CAPACITOR_?_1206250V_0.1UF"))
    )
    (comp (ref "C30")
      (value "CAPACITOR_2220_630V_1UF")
      (footprint "eagle-import:2220-CAP")
      (fields
        (field (name "CAPACITANCE") "1µF")
        (field (name "MANUFACTURER") "Knowles Syfer")
        (field (name "MPN") "2220Y6300105KXTWS2")
        (field (name "TOLERANCE") "10%")
        (field (name "VOLTAGE") "630V")
      )
      (libsource (lib "eagle-import") (part "CAPACITOR_?_2220630V_1UF"))
    )
    (comp (ref "C31")
      (value "CAPACITOR_2220_250V_1UF")
      (footprint "eagle-import:2220-CAP")
      (fields
        (field (name "CAPACITANCE") "1µF")
        (field (name "MANUFACTURER") "TDK Corporation")
        (field (name "MPN") "C5750X7R2E105K230KA")
        (field (name "TOLERANCE") "10%")
        (field (name "VOLTAGE") "250V")
      )
      (libsource (lib "eagle-import") (part "CAPACITOR_?_2220250V_1UF"))
    )
    (comp (ref "C32")
      (value "CAPACITOR_2220_250V_1UF")
      (footprint "eagle-import:2220-CAP")
      (fields
        (field (name "CAPACITANCE") "1µF")
        (field (name "MANUFACTURER") "TDK Corporation")
        (field (name "MPN") "C5750X7R2E105K230KA")
        (field (name "TOLERANCE") "10%")
        (field (name "VOLTAGE") "250V")
      )
      (libsource (lib "eagle-import") (part "CAPACITOR_?_2220250V_1UF"))
    )
    (comp (ref "C33")
      (value "CAPACITOR_2220_250V_1UF")
      (footprint "eagle-import:2220-CAP")
      (fields
        (field (name "CAPACITANCE") "1µF")
        (field (name "MANUFACTURER") "TDK Corporation")
        (field (name "MPN") "C5750X7R2E105K230KA")
        (field (name "TOLERANCE") "10%")
        (field (name "VOLTAGE") "250V")
      )
      (libsource (lib "eagle-import") (part "CAPACITOR_?_2220250V_1UF"))
    )
    (comp (ref "C34")
      (value "CAPACITOR_0805_25V_22UF")
      (footprint "eagle-import:0805-CAP")
      (fields
        (field (name "CAPACITANCE") "22µF")
        (field (name "MANUFACTURER") "Yageo")
        (field (name "MPN") "CC0805MKX5R8BB226")
        (field (name "TOLERANCE") "20%")
        (field (name "VOLTAGE") "25V")
      )
      (libsource (lib "eagle-import") (part "CAPACITOR_?_080525V_22UF"))
    )
    (comp (ref "C35")
      (value "CAPACITOR_0603_10V_10NF")
      (footprint "eagle-import:0603-CAP")
      (fields
        (field (name "CAPACITANCE") "10nF")
        (field (name "MANUFACTURER") "Yageo")
        (field (name "MPN") "CC0603KRX7R6BB103")
        (field (name "TOLERANCE") "10%")
        (field (name "VOLTAGE") "10V")
      )
      (libsource (lib "eagle-import") (part "CAPACITOR_?_060310V_10NF"))
    )
    (comp (ref "C36")
      (value "CAPACITOR_0603_25V_1UF")
      (footprint "eagle-import:0603-CAP")
      (fields
        (field (name "CAPACITANCE") "1µF")
        (field (name "MANUFACTURER") "Samsung Electro-Mechanics")
        (field (name "MPN") "CL10B105KA8NNNC")
        (field (name "TOLERANCE") "10%")
        (field (name "VOLTAGE") "25V")
      )
      (libsource (lib "eagle-import") (part "CAPACITOR_?_060325V_1UF"))
    )
    (comp (ref "C37")
      (value "CAPACITOR_0603_25V_0.1UF")
      (footprint "eagle-import:0603-CAP")
      (fields
        (field (name "CAPACITANCE") "0.1µF")
        (field (name "MANUFACTURER") "Samsung Electro-Mechanics")
        (field (name "MPN") "CL10B104KA8NNNC")
        (field (name "TOLERANCE") "10%")
        (field (name "VOLTAGE") "25V")
      )
      (libsource (lib "eagle-import") (part "CAPACITOR_?_060325V_0.1UF"))
    )
    (comp (ref "C38")
      (value "CAPACITOR_0603_10V_1UF")
      (footprint "eagle-import:0603-CAP")
      (fields
        (field (name "CAPACITANCE") "1µF")
        (field (name "MANUFACTURER") "Yageo")
        (field (name "MPN") "CC0603KRX7R6BB105")
        (field (name "TOLERANCE") "10%")
        (field (name "VOLTAGE") "10V")
      )
      (libsource (lib "eagle-import") (part "CAPACITOR_?_060310V_1UF"))
    )
    (comp (ref "C39")
      (value "CAPACITOR_0603_10V_1UF")
      (footprint "eagle-import:0603-CAP")
      (fields
        (field (name "CAPACITANCE") "1µF")
        (field (name "MANUFACTURER") "Yageo")
        (field (name "MPN") "CC0603KRX7R6BB105")
        (field (name "TOLERANCE") "10%")
        (field (name "VOLTAGE") "10V")
      )
      (libsource (lib "eagle-import") (part "CAPACITOR_?_060310V_1UF"))
    )
    (comp (ref "C40")
      (value "CAPACITOR_0603_10V_1UF")
      (footprint "eagle-import:0603-CAP")
      (fields
        (field (name "CAPACITANCE") "1µF")
        (field (name "MANUFACTURER") "Yageo")
        (field (name "MPN") "CC0603KRX7R6BB105")
        (field (name "TOLERANCE") "10%")
        (field (name "VOLTAGE") "10V")
      )
      (libsource (lib "eagle-import") (part "CAPACITOR_?_060310V_1UF"))
    )
    (comp (ref "C41")
      (value "CAPACITOR_0603_10V_1UF")
      (footprint "eagle-import:0603-CAP")
      (fields
        (field (name "CAPACITANCE") "1µF")
        (field (name "MANUFACTURER") "Yageo")
        (field (name "MPN") "CC0603KRX7R6BB105")
        (field (name "TOLERANCE") "10%")
        (field (name "VOLTAGE") "10V")
      )
      (libsource (lib "eagle-import") (part "CAPACITOR_?_060310V_1UF"))
    )
    (comp (ref "C42")
      (value "CAPACITOR_0603_10V_0.1UF")
      (footprint "eagle-import:0603-CAP")
      (fields
        (field (name "CAPACITANCE") "0.1µF")
        (field (name "MANUFACTURER") "Vishay Vitramon")
        (field (name "MPN") "VJ0603Y104JXQPW1BC")
        (field (name "TOLERANCE") "5%")
        (field (name "VOLTAGE") "10V")
      )
      (libsource (lib "eagle-import") (part "CAPACITOR_?_060310V_0.1UF"))
    )
    (comp (ref "C43")
      (value "CAPACITOR_0603_10V_0.1UF")
      (footprint "eagle-import:0603-CAP")
      (fields
        (field (name "CAPACITANCE") "0.1µF")
        (field (name "MANUFACTURER") "Vishay Vitramon")
        (field (name "MPN") "VJ0603Y104JXQPW1BC")
        (field (name "TOLERANCE") "5%")
        (field (name "VOLTAGE") "10V")
      )
      (libsource (lib "eagle-import") (part "CAPACITOR_?_060310V_0.1UF"))
    )
    (comp (ref "C44")
      (value "CAPACITOR_0603_10V_1UF")
      (footprint "eagle-import:0603-CAP")
      (fields
        (field (name "CAPACITANCE") "1µF")
        (field (name "MANUFACTURER") "Yageo")
        (field (name "MPN") "CC0603KRX7R6BB105")
        (field (name "TOLERANCE") "10%")
        (field (name "VOLTAGE") "10V")
      )
      (libsource (lib "eagle-import") (part "CAPACITOR_?_060310V_1UF"))
    )
    (comp (ref "C45")
      (value "CAPACITOR_0603_10V_1UF")
      (footprint "eagle-import:0603-CAP")
      (fields
        (field (name "CAPACITANCE") "1µF")
        (field (name "MANUFACTURER") "Yageo")
        (field (name "MPN") "CC0603KRX7R6BB105")
        (field (name "TOLERANCE") "10%")
        (field (name "VOLTAGE") "10V")
      )
      (libsource (lib "eagle-import") (part "CAPACITOR_?_060310V_1UF"))
    )
    (comp (ref "C46")
      (value "CAPACITOR_0603_10V_1UF")
      (footprint "eagle-import:0603-CAP")
      (fields
        (field (name "CAPACITANCE") "1µF")
        (field (name "MANUFACTURER") "Yageo")
        (field (name "MPN") "CC0603KRX7R6BB105")
        (field (name "TOLERANCE") "10%")
        (field (name "VOLTAGE") "10V")
      )
      (libsource (lib "eagle-import") (part "CAPACITOR_?_060310V_1UF"))
    )
    (comp (ref "C47")
      (value "CAPACITOR_0603_10V_1UF")
      (footprint "eagle-import:0603-CAP")
      (fields
        (field (name "CAPACITANCE") "1µF")
        (field (name "MANUFACTURER") "Yageo")
        (field (name "MPN") "CC0603KRX7R6BB105")
        (field (name "TOLERANCE") "10%")
        (field (name "VOLTAGE") "10V")
      )
      (libsource (lib "eagle-import") (part "CAPACITOR_?_060310V_1UF"))
    )
    (comp (ref "C48")
      (value "CAPACITOR_0603_10V_10NF")
      (footprint "eagle-import:0603-CAP")
      (fields
        (field (name "CAPACITANCE") "10nF")
        (field (name "MANUFACTURER") "Yageo")
        (field (name "MPN") "CC0603KRX7R6BB103")
        (field (name "TOLERANCE") "10%")
        (field (name "VOLTAGE") "10V")
      )
      (libsource (lib "eagle-import") (part "CAPACITOR_?_060310V_10NF"))
    )
    (comp (ref "C49")
      (value "CAPACITOR_0603_10V_10NF")
      (footprint "eagle-import:0603-CAP")
      (fields
        (field (name "CAPACITANCE") "10nF")
        (field (name "MANUFACTURER") "Yageo")
        (field (name "MPN") "CC0603KRX7R6BB103")
        (field (name "TOLERANCE") "10%")
        (field (name "VOLTAGE") "10V")
      )
      (libsource (lib "eagle-import") (part "CAPACITOR_?_060310V_10NF"))
    )
    (comp (ref "D10")
      (value "SCHOTTKY")
      (footprint "eagle-import:CLP1608-2L")
      (fields
        (field (name "MPN") "VSKY20401608-G4-08")
        (field (name "MANUFACTURER") "Vishay General Semiconductor - Diodes Division")
      )
      (libsource (lib "eagle-import") (part "SCHOTTKY"))
    )
    (comp (ref "D13")
      (value "LED_0603_BLUE")
      (footprint "eagle-import:0603-LED")
      (fields
        (field (name "COLOR") "Blue")
        (field (name "MANUFACTURER") "Kingbright")
        (field (name "MPN") "APT1608VBC/D")
      )
      (libsource (lib "eagle-import") (part "LED_?_0603BLUE"))
    )
    (comp (ref "L6")
      (value "INDUCTOR_SRU1048_330UH")
      (footprint "eagle-import:SRU1048")
      (fields
        (field (name "INDUCTANCE") "330µH")
        (field (name "MANUFACTURER") "Bourns Inc.")
        (field (name "MPN") "SRU1048-331Y")
        (field (name "TOLERANCE") "30%")
      )
      (libsource (lib "eagle-import") (part "INDUCTOR_?_SRU1048330UH"))
    )
    (comp (ref "R1")
      (value "RESISTOR_0603_5.9K")
      (footprint "eagle-import:0603-RES")
      (fields
        (field (name "MANUFACTURER") "Panasonic Electronic Components")
        (field (name "MPN") "ERA-3AEB5901V")
        (field (name "POWER") "0.1W")
        (field (name "RESISTANCE") "5.9k")
      )
      (libsource (lib "eagle-import") (part "RESISTOR_?_06035.9K"))
    )
    (comp (ref "R2")
      (value "RESISTOR_0603_5.9K")
      (footprint "eagle-import:0603-RES")
      (fields
        (field (name "MANUFACTURER") "Panasonic Electronic Components")
        (field (name "MPN") "ERA-3AEB5901V")
        (field (name "POWER") "0.1W")
        (field (name "RESISTANCE") "5.9k")
      )
      (libsource (lib "eagle-import") (part "RESISTOR_?_06035.9K"))
    )
    (comp (ref "R3")
      (value "RESISTOR_0603_8.66K")
      (footprint "eagle-import:0603-RES")
      (fields
        (field (name "MANUFACTURER") "Yageo")
        (field (name "MPN") "RT0603BRD078K66L")
        (field (name "POWER") "0.1W")
        (field (name "RESISTANCE") "8.66k")
      )
      (libsource (lib "eagle-import") (part "RESISTOR_?_06038.66K"))
    )
    (comp (ref "R4")
      (value "RESISTOR_0603_13K")
      (footprint "eagle-import:0603-RES")
      (fields
        (field (name "MANUFACTURER") "Panasonic Electronic Components")
        (field (name "MPN") " ERJ-PB3B1302V")
        (field (name "POWER") "0.1W")
        (field (name "RESISTANCE") "13k")
      )
      (libsource (lib "eagle-import") (part "RESISTOR_?_060313K"))
    )
    (comp (ref "R5")
      (value "RESISTOR_0805_976K")
      (footprint "eagle-import:0805-RES")
      (fields
        (field (name "MANUFACTURER") "Panasonic Electronic Components")
        (field (name "MPN") "  ERJ-PB6B9763V")
        (field (name "POWER") "0.25W")
        (field (name "RESISTANCE") "976k")
      )
      (libsource (lib "eagle-import") (part "RESISTOR_?_0805976K"))
    )
    (comp (ref "R6")
      (value "RESISTOR_0805_365K")
      (footprint "eagle-import:0805-RES")
      (fields
        (field (name "MANUFACTURER") "Panasonic Electronic Components")
        (field (name "MPN") "ERJ-PB6B3653V")
        (field (name "POWER") "0.25W")
        (field (name "RESISTANCE") "365k")
      )
      (libsource (lib "eagle-import") (part "RESISTOR_?_0805365K"))
    )
    (comp (ref "R7")
      (value "RESISTOR_0805_365K")
      (footprint "eagle-import:0805-RES")
      (fields
        (field (name "MANUFACTURER") "Panasonic Electronic Components")
        (field (name "MPN") "ERJ-PB6B3653V")
        (field (name "POWER") "0.25W")
        (field (name "RESISTANCE") "365k")
      )
      (libsource (lib "eagle-import") (part "RESISTOR_?_0805365K"))
    )
    (comp (ref "R8")
      (value "RESISTOR_0805_365K")
      (footprint "eagle-import:0805-RES")
      (fields
        (field (name "MANUFACTURER") "Panasonic Electronic Components")
        (field (name "MPN") "ERJ-PB6B3653V")
        (field (name "POWER") "0.25W")
        (field (name "RESISTANCE") "365k")
      )
      (libsource (lib "eagle-import") (part "RESISTOR_?_0805365K"))
    )
    (comp (ref "R9")
      (value "RESISTOR_0805_365K")
      (footprint "eagle-import:0805-RES")
      (fields
        (field (name "MANUFACTURER") "Panasonic Electronic Components")
        (field (name "MPN") "ERJ-PB6B3653V")
        (field (name "POWER") "0.25W")
        (field (name "RESISTANCE") "365k")
      )
      (libsource (lib "eagle-import") (part "RESISTOR_?_0805365K"))
    )
    (comp (ref "R10")
      (value "RESISTOR_0603_33.2K")
      (footprint "eagle-import:0603-RES")
      (fields
        (field (name "MANUFACTURER") "Panasonic Electronic Components")
        (field (name "MPN") "ERJ-PB3B3322V")
        (field (name "POWER") "0.1W")
        (field (name "RESISTANCE") "33.2k")
      )
      (libsource (lib "eagle-import") (part "RESISTOR_?_060333.2K"))
    )
    (comp (ref "R11")
      (value "RESISTOR_0603_33.2K")
      (footprint "eagle-import:0603-RES")
      (fields
        (field (name "MANUFACTURER") "Panasonic Electronic Components")
        (field (name "MPN") "ERJ-PB3B3322V")
        (field (name "POWER") "0.1W")
        (field (name "RESISTANCE") "33.2k")
      )
      (libsource (lib "eagle-import") (part "RESISTOR_?_060333.2K"))
    )
    (comp (ref "R12")
      (value "RESISTOR_0603_33.2K")
      (footprint "eagle-import:0603-RES")
      (fields
        (field (name "MANUFACTURER") "Panasonic Electronic Components")
        (field (name "MPN") "ERJ-PB3B3322V")
        (field (name "POWER") "0.1W")
        (field (name "RESISTANCE") "33.2k")
      )
      (libsource (lib "eagle-import") (part "RESISTOR_?_060333.2K"))
    )
    (comp (ref "R13")
      (value "RESISTOR_0603_33.2K")
      (footprint "eagle-import:0603-RES")
      (fields
        (field (name "MANUFACTURER") "Panasonic Electronic Components")
        (field (name "MPN") "ERJ-PB3B3322V")
        (field (name "POWER") "0.1W")
        (field (name "RESISTANCE") "33.2k")
      )
      (libsource (lib "eagle-import") (part "RESISTOR_?_060333.2K"))
    )
    (comp (ref "R14")
      (value "RESISTOR_0603_33.2K")
      (footprint "eagle-import:0603-RES")
      (fields
        (field (name "MANUFACTURER") "Panasonic Electronic Components")
        (field (name "MPN") "ERJ-PB3B3322V")
        (field (name "POWER") "0.1W")
        (field (name "RESISTANCE") "33.2k")
      )
      (libsource (lib "eagle-import") (part "RESISTOR_?_060333.2K"))
    )
    (comp (ref "R15")
      (value "RESISTOR_0603_33.2K")
      (footprint "eagle-import:0603-RES")
      (fields
        (field (name "MANUFACTURER") "Panasonic Electronic Components")
        (field (name "MPN") "ERJ-PB3B3322V")
        (field (name "POWER") "0.1W")
        (field (name "RESISTANCE") "33.2k")
      )
      (libsource (lib "eagle-import") (part "RESISTOR_?_060333.2K"))
    )
    (comp (ref "R16")
      (value "RESISTOR_0805_365K")
      (footprint "eagle-import:0805-RES")
      (fields
        (field (name "MANUFACTURER") "Panasonic Electronic Components")
        (field (name "MPN") "ERJ-PB6B3653V")
        (field (name "POWER") "0.25W")
        (field (name "RESISTANCE") "365k")
      )
      (libsource (lib "eagle-import") (part "RESISTOR_?_0805365K"))
    )
    (comp (ref "R17")
      (value "RESISTOR_0805_365K")
      (footprint "eagle-import:0805-RES")
      (fields
        (field (name "MANUFACTURER") "Panasonic Electronic Components")
        (field (name "MPN") "ERJ-PB6B3653V")
        (field (name "POWER") "0.25W")
        (field (name "RESISTANCE") "365k")
      )
      (libsource (lib "eagle-import") (part "RESISTOR_?_0805365K"))
    )
    (comp (ref "R18")
      (value "RESISTOR_0805_365K")
      (footprint "eagle-import:0805-RES")
      (fields
        (field (name "MANUFACTURER") "Panasonic Electronic Components")
        (field (name "MPN") "ERJ-PB6B3653V")
        (field (name "POWER") "0.25W")
        (field (name "RESISTANCE") "365k")
      )
      (libsource (lib "eagle-import") (part "RESISTOR_?_0805365K"))
    )
    (comp (ref "R19")
      (value "RESISTOR_0805_365K")
      (footprint "eagle-import:0805-RES")
      (fields
        (field (name "MANUFACTURER") "Panasonic Electronic Components")
        (field (name "MPN") "ERJ-PB6B3653V")
        (field (name "POWER") "0.25W")
        (field (name "RESISTANCE") "365k")
      )
      (libsource (lib "eagle-import") (part "RESISTOR_?_0805365K"))
    )
    (comp (ref "R20")
      (value "RESISTOR_0603_33.2K")
      (footprint "eagle-import:0603-RES")
      (fields
        (field (name "MANUFACTURER") "Panasonic Electronic Components")
        (field (name "MPN") "ERJ-PB3B3322V")
        (field (name "POWER") "0.1W")
        (field (name "RESISTANCE") "33.2k")
      )
      (libsource (lib "eagle-import") (part "RESISTOR_?_060333.2K"))
    )
    (comp (ref "R21")
      (value "RESISTOR_0603_33.2K")
      (footprint "eagle-import:0603-RES")
      (fields
        (field (name "MANUFACTURER") "Panasonic Electronic Components")
        (field (name "MPN") "ERJ-PB3B3322V")
        (field (name "POWER") "0.1W")
        (field (name "RESISTANCE") "33.2k")
      )
      (libsource (lib "eagle-import") (part "RESISTOR_?_060333.2K"))
    )
    (comp (ref "R22")
      (value "RESISTOR_0603_33.2K")
      (footprint "eagle-import:0603-RES")
      (fields
        (field (name "MANUFACTURER") "Panasonic Electronic Components")
        (field (name "MPN") "ERJ-PB3B3322V")
        (field (name "POWER") "0.1W")
        (field (name "RESISTANCE") "33.2k")
      )
      (libsource (lib "eagle-import") (part "RESISTOR_?_060333.2K"))
    )
    (comp (ref "R23")
      (value "RESISTOR_0603_33.2K")
      (footprint "eagle-import:0603-RES")
      (fields
        (field (name "MANUFACTURER") "Panasonic Electronic Components")
        (field (name "MPN") "ERJ-PB3B3322V")
        (field (name "POWER") "0.1W")
        (field (name "RESISTANCE") "33.2k")
      )
      (libsource (lib "eagle-import") (part "RESISTOR_?_060333.2K"))
    )
    (comp (ref "R24")
      (value "RESISTOR_0603_33.2K")
      (footprint "eagle-import:0603-RES")
      (fields
        (field (name "MANUFACTURER") "Panasonic Electronic Components")
        (field (name "MPN") "ERJ-PB3B3322V")
        (field (name "POWER") "0.1W")
        (field (name "RESISTANCE") "33.2k")
      )
      (libsource (lib "eagle-import") (part "RESISTOR_?_060333.2K"))
    )
    (comp (ref "R25")
      (value "RESISTOR_0603_33.2K")
      (footprint "eagle-import:0603-RES")
      (fields
        (field (name "MANUFACTURER") "Panasonic Electronic Components")
        (field (name "MPN") "ERJ-PB3B3322V")
        (field (name "POWER") "0.1W")
        (field (name "RESISTANCE") "33.2k")
      )
      (libsource (lib "eagle-import") (part "RESISTOR_?_060333.2K"))
    )
    (comp (ref "R26")
      (value "RESISTOR_0805_1")
      (footprint "eagle-import:0805-RES")
      (fields
        (field (name "MANUFACTURER") "Panasonic Electronic Components")
        (field (name "MPN") "ERJ-6RQF1R0V")
        (field (name "POWER") "0.125W")
        (field (name "RESISTANCE") "1")
      )
      (libsource (lib "eagle-import") (part "RESISTOR_?_08051"))
    )
    (comp (ref "R43")
      (value "RESISTOR_0805_365K")
      (footprint "eagle-import:0805-RES")
      (fields
        (field (name "MANUFACTURER") "Panasonic Electronic Components")
        (field (name "MPN") "ERJ-PB6B3653V")
        (field (name "POWER") "0.25W")
        (field (name "RESISTANCE") "365k")
      )
      (libsource (lib "eagle-import") (part "RESISTOR_?_0805365K"))
    )
    (comp (ref "R45")
      (value "RESISTOR_0603_3.32K")
      (footprint "eagle-import:0603-RES")
      (fields
        (field (name "MANUFACTURER") "Yageo")
        (field (name "MPN") "RT0603BRD073K32L")
        (field (name "POWER") "0.1W")
        (field (name "RESISTANCE") "3.32k")
      )
      (libsource (lib "eagle-import") (part "RESISTOR_?_06033.32K"))
    )
    (comp (ref "R47")
      (value "RESISTOR_0603_10K")
      (footprint "eagle-import:0603-RES")
      (fields
        (field (name "MANUFACTURER") "Yageo")
        (field (name "MPN") "RC0603FR-0710KL")
        (field (name "POWER") "0.1W")
        (field (name "RESISTANCE") "10k")
      )
      (libsource (lib "eagle-import") (part "RESISTOR_?_060310K"))
    )
    (comp (ref "R48")
      (value "RESISTOR_0603_75K")
      (footprint "eagle-import:0603-RES")
      (fields
        (field (name "MANUFACTURER") "Yageo")
        (field (name "MPN") "RT0603BRE0775KL")
        (field (name "POWER") "0.1W")
        (field (name "RESISTANCE") "75k")
      )
      (libsource (lib "eagle-import") (part "RESISTOR_?_060375K"))
    )
    (comp (ref "R49")
      (value "RESISTOR_0603_33.2K")
      (footprint "eagle-import:0603-RES")
      (fields
        (field (name "MANUFACTURER") "Panasonic Electronic Components")
        (field (name "MPN") "ERJ-PB3B3322V")
        (field (name "POWER") "0.1W")
        (field (name "RESISTANCE") "33.2k")
      )
      (libsource (lib "eagle-import") (part "RESISTOR_?_060333.2K"))
    )
    (comp (ref "R50")
      (value "RESISTOR_0603_33.2K")
      (footprint "eagle-import:0603-RES")
      (fields
        (field (name "MANUFACTURER") "Panasonic Electronic Components")
        (field (name "MPN") "ERJ-PB3B3322V")
        (field (name "POWER") "0.1W")
        (field (name "RESISTANCE") "33.2k")
      )
      (libsource (lib "eagle-import") (part "RESISTOR_?_060333.2K"))
    )
    (comp (ref "R55")
      (value "RESISTOR_0603_1K")
      (footprint "eagle-import:0603-RES")
      (fields
        (field (name "MANUFACTURER") "Yageo")
        (field (name "MPN") "RC0603FR-071KL")
        (field (name "POWER") "0.1W")
        (field (name "RESISTANCE") "1k")
      )
      (libsource (lib "eagle-import") (part "RESISTOR_?_06031K"))
    )
    (comp (ref "U16")
      (value "LTC3639")
      (footprint "eagle-import:MSE16(12)")
      (fields (field (name "MPN") "LTC3639EMSE#TRPBF ") (field (name "MANUFACTURER") "Analog Devices Inc."))
      (libsource (lib "eagle-import") (part "LTC3639"))
    )
    (comp (ref "U17")
      (value "VOLTAGE_REGULATOR_ADJ_LR8_DPAK")
      (footprint "eagle-import:DPAK(2-7K1S)")
      (fields (field (name "MANUFACTURER") "Microchip Technology") (field (name "MPN") "LR8K4-G"))
      (libsource (lib "eagle-import") (part "VOLTAGE_REGULATOR_ADJ__?DPAKLR8"))
    )
    (comp (ref "U18")
      (value "ISO224B_AIRGAP")
      (footprint "eagle-import:SOIC-08(WIDE,0.295_)-AIRGAP")
      (fields (field (name "MANUFACTURER") "Texas Instruments") (field (name "MPN") "ISO224BDWVR"))
      (libsource (lib "eagle-import") (part "ISO224_AIRGAPB"))
    )
    (comp (ref "U19")
      (value "ISO224B_AIRGAP")
      (footprint "eagle-import:SOIC-08(WIDE,0.295_)-AIRGAP")
      (fields (field (name "MANUFACTURER") "Texas Instruments") (field (name "MPN") "ISO224BDWVR"))
      (libsource (lib "eagle-import") (part "ISO224_AIRGAPB"))
    )
  )
  (nets
    (net (code "1") (name "+12V") (class "Default")
      (node (ref "C6") (pin "1") (pinfunction "1_1") (pintype "passive"))
      (node (ref "C8") (pin "1") (pinfunction "1_1") (pintype "passive"))
      (node (ref "J3") (pin "1") (pinfunction "1_1") (pintype "passive"))
      (node (ref "R35") (pin "2") (pinfunction "2_2") (pintype "passive"))
      (node (ref "TP1") (pin "1") (pinfunction "P$1_1") (pintype "passive"))
      (node (ref "U2") (pin "3") (pinfunction "IN_3") (pintype "power_in"))
    )
    (net (code "2") (name "DCDC+") (class "Default")
      (node (ref "F1") (pin "L1") (pinfunction "1_L1") (pintype "passive"))
      (node (ref "F1") (pin "L2") (pinfunction "1_L2") (pintype "passive"))
      (node (ref "J5") (pin "1") (pinfunction "1_1") (pintype "passive"))
      (node (ref "J5") (pin "3") (pinfunction "3_3") (pintype "passive"))
      (node (ref "R30") (pin "2") (pinfunction "2_2") (pintype "passive"))
      (node (ref "TP9") (pin "1") (pinfunction "P$1_1") (pintype "passive"))
    )
    (net (code "3") (name "DCDC-") (class "Default")
      (node (ref "C26") (pin "-") (pinfunction "MINUS_-") (pintype "passive"))
      (node (ref "C27") (pin "1") (pinfunction "1_1") (pintype "passive"))
      (node (ref "C28") (pin "1") (pinfunction "1_1") (pintype "passive"))
      (node (ref "C29") (pin "1") (pinfunction "1_1") (pintype "passive"))
      (node (ref "D5") (pin "1") (pinfunction "C_1") (pintype "passive"))
      (node (ref "J5") (pin "2") (pinfunction "2_2") (pintype "passive"))
      (node (ref "J5") (pin "4") (pinfunction "4_4") (pintype "passive"))
      (node (ref "TP10") (pin "1") (pinfunction "P$1_1") (pintype "passive"))
      (node (ref "U10") (pin "7") (pinfunction "-OUT_7") (pintype "power_in"))
      (node (ref "U10") (pin "9") (pinfunction "-OUT_9") (pintype "power_in"))
    )
    (net (code "4") (name "ENABLE") (class "Default")
      (node (ref "R56") (pin "2") (pinfunction "2_2") (pintype "passive"))
      (node (ref "U10") (pin "3") (pinfunction "EN_3") (pintype "input"))
      (node (ref "U11") (pin "4") (pinfunction "CONTACT2_4") (pintype "bidirectional"))
    )
    (net (code "5") (name "GND") (class "Default")
      (node (ref "C41") (pin "2") (pinfunction "2_2") (pintype "passive"))
      (node (ref "C42") (pin "2") (pinfunction "2_2") (pintype "passive"))
      (node (ref "C43") (pin "2") (pinfunction "2_2") (pintype "passive"))
      (node (ref "C44") (pin "2") (pinfunction "2_2") (pintype "passive"))
      (node (ref "C5") (pin "2") (pinfunction "2_2") (pintype "passive"))
      (node (ref "C6") (pin "2") (pinfunction "2_2") (pintype "passive"))
      (node (ref "C7") (pin "2") (pinfunction "2_2") (pintype "passive"))
      (node (ref "C8") (pin "2") (pinfunction "2_2") (pintype "passive"))
      (node (ref "C9") (pin "2") (pinfunction "2_2") (pintype "passive"))
      (node (ref "D1") (pin "1") (pinfunction "A_1") (pintype "passive"))
      (node (ref "D11") (pin "1") (pinfunction "C_1") (pintype "passive"))
      (node (ref "D12") (pin "1") (pinfunction "C_1") (pintype "passive"))
      (node (ref "D2") (pin "1") (pinfunction "C_1") (pintype "passive"))
      (node (ref "D3") (pin "1") (pinfunction "C_1") (pintype "passive"))
      (node (ref "D4") (pin "1") (pinfunction "C_1") (pintype "passive"))
      (node (ref "D7") (pin "2") (pinfunction "A_2") (pintype "passive"))
      (node (ref "D9") (pin "1") (pinfunction "C_1") (pintype "passive"))
      (node (ref "J3") (pin "4") (pinfunction "4_4") (pintype "passive"))
      (node (ref "K4") (pin "3") (pinfunction "COIL-_3") (pintype "bidirectional"))
      (node (ref "Q2") (pin "2") (pinfunction "S_2") (pintype "passive"))
      (node (ref "R38") (pin "1") (pinfunction "1_1") (pintype "passive"))
      (node (ref "R46") (pin "1") (pinfunction "1_1") (pintype "passive"))
      (node (ref "R51") (pin "1") (pinfunction "1_1") (pintype "passive"))
      (node (ref "TP3") (pin "1") (pinfunction "P$1_1") (pintype "passive"))
      (node (ref "U$1") (pin "2") (pinfunction "CONTROL-_2") (pintype "passive"))
      (node (ref "U1") (pin "2") (pinfunction "GND_2") (pintype "power_in"))
      (node (ref "U11") (pin "2") (pinfunction "CONTROL-_2") (pintype "passive"))
      (node (ref "U15") (pin "3") (pinfunction "GND_3") (pintype "power_in"))
      (node (ref "U18") (pin "5") (pinfunction "GND2_5") (pintype "power_in"))
      (node (ref "U19") (pin "5") (pinfunction "GND2_5") (pintype "power_in"))
      (node (ref "U2") (pin "1") (pinfunction "GND_1") (pintype "power_in"))
    )
    (net (code "6") (name "IP+") (class "Default")
      (node (ref "J3") (pin "5") (pinfunction "5_5") (pintype "passive"))
      (node (ref "TP5") (pin "1") (pinfunction "P$1_1") (pintype "passive"))
      (node (ref "U19") (pin "7") (pinfunction "OUTP_7") (pintype "output"))
    )
    (net (code "7") (name "IP-") (class "Default")
      (node (ref "J3") (pin "6") (pinfunction "6_6") (pintype "passive"))
      (node (ref "TP6") (pin "1") (pinfunction "P$1_1") (pintype "passive"))
      (node (ref "U19") (pin "6") (pinfunction "OUTN_6") (pintype "output"))
    )
    (net (code "8") (name "IT+") (class "Default")
      (node (ref "J3") (pin "7") (pinfunction "7_7") (pintype "passive"))
      (node (ref "TP7") (pin "1") (pinfunction "P$1_1") (pintype "passive"))
      (node (ref "U18") (pin "7") (pinfunction "OUTP_7") (pintype "output"))
    )
    (net (code "9") (name "IT-") (class "Default")
      (node (ref "J3") (pin "8") (pinfunction "8_8") (pintype "passive"))
      (node (ref "TP8") (pin "1") (pinfunction "P$1_1") (pintype "passive"))
      (node (ref "U18") (pin "6") (pinfunction "OUTN_6") (pintype "output"))
    )
    (net (code "10") (name "LED+") (class "Default")
      (node (ref "R63") (pin "2") (pinfunction "2_2") (pintype "passive"))
      (node (ref "U$31") (pin "3") (pinfunction "3_3") (pintype "passive"))
    )
    (net (code "11") (name "Net-(C26-PLUS)") (class "Default")
      (node (ref "C26") (pin "+") (pinfunction "PLUS_+") (pintype "passive"))
      (node (ref "C27") (pin "2") (pinfunction "2_2") (pintype "passive"))
      (node (ref "C28") (pin "2") (pinfunction "2_2") (pintype "passive"))
      (node (ref "C29") (pin "2") (pinfunction "2_2") (pintype "passive"))
      (node (ref "F1") (pin "R1") (pinfunction "2_R1") (pintype "passive"))
      (node (ref "F1") (pin "R2") (pinfunction "2_R2") (pintype "passive"))
      (node (ref "U10") (pin "6") (pinfunction "+OUT_6") (pintype "power_in"))
      (node (ref "U10") (pin "8") (pinfunction "+OUT_8") (pintype "power_in"))
    )
    (net (code "12") (name "Net-(C35-Pad2)") (class "Default")
      (node (ref "C35") (pin "2") (pinfunction "2_2") (pintype "passive"))
      (node (ref "R47") (pin "2") (pinfunction "2_2") (pintype "passive"))
    )
    (net (code "13") (name "Net-(D1-C)") (class "Default")
      (node (ref "D1") (pin "3") (pinfunction "C_3") (pintype "passive"))
      (node (ref "R37") (pin "1") (pinfunction "1_1") (pintype "passive"))
      (node (ref "R38") (pin "2") (pinfunction "2_2") (pintype "passive"))
      (node (ref "R52") (pin "2") (pinfunction "2_2") (pintype "passive"))
      (node (ref "U15") (pin "4") (pinfunction "~{IN}_4") (pintype "output"))
    )
    (net (code "14") (name "Net-(D2-A)") (class "Default")
      (node (ref "D2") (pin "2") (pinfunction "A_2") (pintype "passive"))
      (node (ref "R28") (pin "1") (pinfunction "1_1") (pintype "passive"))
    )
    (net (code "15") (name "Net-(D3-A)") (class "Default")
      (node (ref "D3") (pin "2") (pinfunction "A_2") (pintype "passive"))
      (node (ref "R29") (pin "1") (pinfunction "1_1") (pintype "passive"))
    )
    (net (code "16") (name "Net-(D4-A)") (class "Default")
      (node (ref "D4") (pin "2") (pinfunction "A_2") (pintype "passive"))
      (node (ref "R52") (pin "1") (pinfunction "1_1") (pintype "passive"))
    )
    (net (code "17") (name "Net-(D5-A)") (class "Default")
      (node (ref "D5") (pin "2") (pinfunction "A_2") (pintype "passive"))
      (node (ref "R30") (pin "1") (pinfunction "1_1") (pintype "passive"))
    )
    (net (code "18") (name "Net-(D6-A)") (class "Default")
      (node (ref "D6") (pin "2") (pinfunction "A_2") (pintype "passive"))
      (node (ref "R32") (pin "2") (pinfunction "2_2") (pintype "passive"))
    )
    (net (code "19") (name "Net-(D8-A)") (class "Default")
      (node (ref "D8") (pin "2") (pinfunction "A_2") (pintype "passive"))
      (node (ref "K5") (pin "3") (pinfunction "COIL-_3") (pintype "bidirectional"))
      (node (ref "Q2") (pin "3") (pinfunction "D_3") (pintype "passive"))
    )
    (net (code "20") (name "Net-(D9-A)") (class "Default")
      (node (ref "D9") (pin "2") (pinfunction "A_2") (pintype "passive"))
      (node (ref "R35") (pin "1") (pinfunction "1_1") (pintype "passive"))
    )
    (net (code "21") (name "Net-(D10-A)") (class "Default")
      (node (ref "C3") (pin "1") (pinfunction "1_1") (pintype "passive"))
      (node (ref "C31") (pin "1") (pinfunction "1_1") (pintype "passive"))
      (node (ref "D10") (pin "2") (pinfunction "A_2") (pintype "passive"))
      (node (ref "R43") (pin "2") (pinfunction "2_2") (pintype "passive"))
      (node (ref "R47") (pin "1") (pinfunction "1_1") (pintype "passive"))
      (node (ref "U17") (pin "2") (pinfunction "OUT_2") (pintype "power_in"))
    )
    (net (code "22") (name "Net-(D10-C)") (class "Default")
      (node (ref "C32") (pin "1") (pinfunction "1_1") (pintype "passive"))
      (node (ref "C33") (pin "1") (pinfunction "1_1") (pintype "passive"))
      (node (ref "C35") (pin "1") (pinfunction "1_1") (pintype "passive"))
      (node (ref "C4") (pin "1") (pinfunction "1_1") (pintype "passive"))
      (node (ref "D10") (pin "1") (pinfunction "C_1") (pintype "passive"))
      (node (ref "R5") (pin "2") (pinfunction "2_2") (pintype "passive"))
      (node (ref "U16") (pin "3") (pinfunction "VDD_3") (pintype "power_in"))
    )
    (net (code "23") (name "Net-(D11-A)") (class "Default")
      (node (ref "D11") (pin "2") (pinfunction "A_2") (pintype "passive"))
      (node (ref "R53") (pin "2") (pinfunction "2_2") (pintype "passive"))
    )
    (net (code "24") (name "Net-(D12-A)") (class "Default")
      (node (ref "D12") (pin "2") (pinfunction "A_2") (pintype "passive"))
      (node (ref "R54") (pin "1") (pinfunction "1_1") (pintype "passive"))
    )
    (net (code "25") (name "Net-(D13-A)") (class "Default")
      (node (ref "D13") (pin "2") (pinfunction "A_2") (pintype "passive"))
      (node (ref "R55") (pin "1") (pinfunction "1_1") (pintype "passive"))
    )
    (net (code "26") (name "Net-(D14-A)") (class "Default")
      (node (ref "D14") (pin "2") (pinfunction "A_2") (pintype "passive"))
      (node (ref "R56") (pin "1") (pinfunction "1_1") (pintype "passive"))
    )
    (net (code "27") (name "Net-(K4-CONTACT2)") (class "Default")
      (node (ref "K4") (pin "4") (pinfunction "CONTACT2_4") (pintype "bidirectional"))
      (node (ref "R40") (pin "1") (pinfunction "1_1") (pintype "passive"))
    )
    (net (code "28") (name "Net-(K5-CONTACT2)") (class "Default")
      (node (ref "K5") (pin "4") (pinfunction "CONTACT2_4") (pintype "bidirectional"))
      (node (ref "R39") (pin "1") (pinfunction "1_1") (pintype "passive"))
    )
    (net (code "29") (name "Net-(L4-Pad2)") (class "Default")
      (node (ref "L4") (pin "2") (pinfunction "2_2") (pintype "passive"))
      (node (ref "R31") (pin "1") (pinfunction "1_1") (pintype "passive"))
    )
    (net (code "30") (name "Net-(Q2-G)") (class "Default")
      (node (ref "Q2") (pin "1") (pinfunction "G_1") (pintype "passive"))
      (node (ref "R37") (pin "2") (pinfunction "2_2") (pintype "passive"))
    )
    (net (code "31") (name "Net-(R1-Pad1)") (class "Default")
      (node (ref "R1") (pin "1") (pinfunction "1_1") (pintype "passive"))
      (node (ref "R16") (pin "1") (pinfunction "1_1") (pintype "passive"))
    )
    (net (code "32") (name "Net-(R2-Pad1)") (class "Default")
      (node (ref "R2") (pin "1") (pinfunction "1_1") (pintype "passive"))
      (node (ref "R6") (pin "1") (pinfunction "1_1") (pintype "passive"))
    )
    (net (code "33") (name "Net-(R6-Pad2)") (class "Default")
      (node (ref "R6") (pin "2") (pinfunction "2_2") (pintype "passive"))
      (node (ref "R7") (pin "2") (pinfunction "2_2") (pintype "passive"))
    )
    (net (code "34") (name "Net-(R7-Pad1)") (class "Default")
      (node (ref "R7") (pin "1") (pinfunction "1_1") (pintype "passive"))
      (node (ref "R8") (pin "1") (pinfunction "1_1") (pintype "passive"))
    )
    (net (code "35") (name "Net-(R8-Pad2)") (class "Default")
      (node (ref "R8") (pin "2") (pinfunction "2_2") (pintype "passive"))
      (node (ref "R9") (pin "2") (pinfunction "2_2") (pintype "passive"))
    )
    (net (code "36") (name "Net-(R10-Pad1)") (class "Default")
      (node (ref "R10") (pin "1") (pinfunction "1_1") (pintype "passive"))
      (node (ref "R11") (pin "1") (pinfunction "1_1") (pintype "passive"))
      (node (ref "R12") (pin "2") (pinfunction "2_2") (pintype "passive"))
      (node (ref "R13") (pin "2") (pinfunction "2_2") (pintype "passive"))
    )
    (net (code "37") (name "Net-(R10-Pad2)") (class "Default")
      (node (ref "R10") (pin "2") (pinfunction "2_2") (pintype "passive"))
      (node (ref "R11") (pin "2") (pinfunction "2_2") (pintype "passive"))
      (node (ref "R49") (pin "1") (pinfunction "1_1") (pintype "passive"))
      (node (ref "R9") (pin "1") (pinfunction "1_1") (pintype "passive"))
    )
    (net (code "38") (name "Net-(R12-Pad1)") (class "Default")
      (node (ref "R12") (pin "1") (pinfunction "1_1") (pintype "passive"))
      (node (ref "R13") (pin "1") (pinfunction "1_1") (pintype "passive"))
      (node (ref "R14") (pin "2") (pinfunction "2_2") (pintype "passive"))
      (node (ref "R15") (pin "2") (pinfunction "2_2") (pintype "passive"))
    )
    (net (code "39") (name "Net-(R16-Pad2)") (class "Default")
      (node (ref "R16") (pin "2") (pinfunction "2_2") (pintype "passive"))
      (node (ref "R17") (pin "2") (pinfunction "2_2") (pintype "passive"))
    )
    (net (code "40") (name "Net-(R17-Pad1)") (class "Default")
      (node (ref "R17") (pin "1") (pinfunction "1_1") (pintype "passive"))
      (node (ref "R18") (pin "1") (pinfunction "1_1") (pintype "passive"))
    )
    (net (code "41") (name "Net-(R18-Pad2)") (class "Default")
      (node (ref "R18") (pin "2") (pinfunction "2_2") (pintype "passive"))
      (node (ref "R19") (pin "2") (pinfunction "2_2") (pintype "passive"))
    )
    (net (code "42") (name "Net-(R19-Pad1)") (class "Default")
      (node (ref "R19") (pin "1") (pinfunction "1_1") (pintype "passive"))
      (node (ref "R20") (pin "2") (pinfunction "2_2") (pintype "passive"))
      (node (ref "R21") (pin "2") (pinfunction "2_2") (pintype "passive"))
      (node (ref "R50") (pin "1") (pinfunction "1_1") (pintype "passive"))
    )
    (net (code "43") (name "Net-(R20-Pad1)") (class "Default")
      (node (ref "R20") (pin "1") (pinfunction "1_1") (pintype "passive"))
      (node (ref "R21") (pin "1") (pinfunction "1_1") (pintype "passive"))
      (node (ref "R22") (pin "2") (pinfunction "2_2") (pintype "passive"))
      (node (ref "R23") (pin "2") (pinfunction "2_2") (pintype "passive"))
    )
    (net (code "44") (name "Net-(R22-Pad1)") (class "Default")
      (node (ref "R22") (pin "1") (pinfunction "1_1") (pintype "passive"))
      (node (ref "R23") (pin "1") (pinfunction "1_1") (pintype "passive"))
      (node (ref "R24") (pin "2") (pinfunction "2_2") (pintype "passive"))
      (node (ref "R25") (pin "2") (pinfunction "2_2") (pintype "passive"))
    )
    (net (code "45") (name "Net-(U$1-CONTACT1)") (class "Default")
      (node (ref "R27") (pin "2") (pinfunction "2_2") (pintype "passive"))
      (node (ref "U$1") (pin "3") (pinfunction "CONTACT1_3") (pintype "bidirectional"))
    )
    (net (code "46") (name "Net-(U$1-CONTROL+)") (class "Default")
      (node (ref "R36") (pin "1") (pinfunction "1_1") (pintype "passive"))
      (node (ref "U$1") (pin "1") (pinfunction "CONTROL+_1") (pintype "passive"))
    )
    (net (code "47") (name "Net-(U1-DIV)") (class "Default")
      (node (ref "R44") (pin "1") (pinfunction "1_1") (pintype "passive"))
      (node (ref "R46") (pin "2") (pinfunction "2_2") (pintype "passive"))
      (node (ref "U1") (pin "6") (pinfunction "DIV_6") (pintype "bidirectional"))
    )
    (net (code "48") (name "Net-(U1-OUT)") (class "Default")
      (node (ref "R28") (pin "2") (pinfunction "2_2") (pintype "passive"))
      (node (ref "R34") (pin "1") (pinfunction "1_1") (pintype "passive"))
      (node (ref "U1") (pin "4") (pinfunction "OUT_4") (pintype "bidirectional"))
    )
    (net (code "49") (name "Net-(U1-SET)") (class "Default")
      (node (ref "R51") (pin "2") (pinfunction "2_2") (pintype "passive"))
      (node (ref "U1") (pin "3") (pinfunction "SET_3") (pintype "bidirectional"))
    )
    (net (code "50") (name "Net-(U10-+IN)") (class "Default")
      (node (ref "C1") (pin "1") (pinfunction "1_1") (pintype "passive"))
      (node (ref "C24") (pin "1") (pinfunction "1_1") (pintype "passive"))
      (node (ref "C25") (pin "1") (pinfunction "1_1") (pintype "passive"))
      (node (ref "L4") (pin "1") (pinfunction "1_1") (pintype "passive"))
      (node (ref "L5") (pin "1") (pinfunction "1_1") (pintype "passive"))
      (node (ref "U10") (pin "1") (pinfunction "+IN_1") (pintype "power_in"))
    )
    (net (code "51") (name "Net-(U10-FLT)") (class "Default")
      (node (ref "R32") (pin "1") (pinfunction "1_1") (pintype "passive"))
      (node (ref "U10") (pin "4") (pinfunction "FLT_4") (pintype "output"))
    )
    (net (code "52") (name "Net-(U10-TR)") (class "Default")
      (node (ref "R33") (pin "1") (pinfunction "1_1") (pintype "passive"))
      (node (ref "U10") (pin "2") (pinfunction "TR_2") (pintype "output"))
    )
    (net (code "53") (name "Net-(U11-CONTROL+)") (class "Default")
      (node (ref "R34") (pin "2") (pinfunction "2_2") (pintype "passive"))
      (node (ref "U11") (pin "1") (pinfunction "CONTROL+_1") (pintype "passive"))
    )
    (net (code "54") (name "Net-(U16-ISET)") (class "Default")
      (node (ref "R48") (pin "2") (pinfunction "2_2") (pintype "passive"))
      (node (ref "U16") (pin "11") (pinfunction "ISET_11") (pintype "bidirectional"))
    )
    (net (code "55") (name "Net-(U16-OVLO)") (class "Default")
      (node (ref "R3") (pin "2") (pinfunction "2_2") (pintype "passive"))
      (node (ref "R4") (pin "1") (pinfunction "1_1") (pintype "passive"))
      (node (ref "U16") (pin "12") (pinfunction "OVLO_12") (pintype "input"))
    )
    (net (code "56") (name "Net-(U16-RUN)") (class "Default")
      (node (ref "R4") (pin "2") (pinfunction "2_2") (pintype "passive"))
      (node (ref "R5") (pin "1") (pinfunction "1_1") (pintype "passive"))
      (node (ref "U16") (pin "14") (pinfunction "RUN_14") (pintype "input"))
    )
    (net (code "57") (name "Net-(U16-SS)") (class "Default")
      (node (ref "U16") (pin "10") (pinfunction "SS_10") (pintype "input"))
      (node (ref "U16") (pin "7") (pinfunction "VPRG1_7") (pintype "input"))
    )
    (net (code "58") (name "Net-(U16-SW)") (class "Default")
      (node (ref "L6") (pin "1") (pinfunction "1_1") (pintype "passive"))
      (node (ref "U16") (pin "1") (pinfunction "SW_1") (pintype "power_in"))
    )
    (net (code "59") (name "Net-(U17-ADJ)") (class "Default")
      (node (ref "R43") (pin "1") (pinfunction "1_1") (pintype "passive"))
      (node (ref "R45") (pin "2") (pinfunction "2_2") (pintype "passive"))
      (node (ref "U17") (pin "3") (pinfunction "ADJ_3") (pintype "input"))
    )
    (net (code "60") (name "Net-(U17-IN)") (class "Default")
      (node (ref "C2") (pin "1") (pinfunction "1_1") (pintype "passive"))
      (node (ref "C30") (pin "1") (pinfunction "1_1") (pintype "passive"))
      (node (ref "R26") (pin "2") (pinfunction "2_2") (pintype "passive"))
      (node (ref "U17") (pin "1") (pinfunction "IN_1") (pintype "power_in"))
    )
    (net (code "61") (name "Net-(U18-IN)") (class "Default")
      (node (ref "C49") (pin "1") (pinfunction "1_1") (pintype "passive"))
      (node (ref "R50") (pin "2") (pinfunction "2_2") (pintype "passive"))
      (node (ref "U18") (pin "2") (pinfunction "IN_2") (pintype "input"))
    )
    (net (code "62") (name "Net-(U18-VCAP)") (class "Default")
      (node (ref "C38") (pin "1") (pinfunction "1_1") (pintype "passive"))
      (node (ref "U18") (pin "1") (pinfunction "VCAP_1") (pintype "passive"))
    )
    (net (code "63") (name "Net-(U19-IN)") (class "Default")
      (node (ref "C48") (pin "1") (pinfunction "1_1") (pintype "passive"))
      (node (ref "R49") (pin "2") (pinfunction "2_2") (pintype "passive"))
      (node (ref "U19") (pin "2") (pinfunction "IN_2") (pintype "input"))
    )
    (net (code "64") (name "Net-(U19-VCAP)") (class "Default")
      (node (ref "C45") (pin "1") (pinfunction "1_1") (pintype "passive"))
      (node (ref "U19") (pin "1") (pinfunction "VCAP_1") (pintype "passive"))
    )
    (net (code "65") (name "PACK+") (class "Default")
      (node (ref "K5") (pin "1") (pinfunction "CONTACT1_1") (pintype "bidirectional"))
      (node (ref "TP12") (pin "1") (pinfunction "P$1_1") (pintype "passive"))
      (node (ref "U$1") (pin "4") (pinfunction "CONTACT2_4") (pintype "bidirectional"))
      (node (ref "U$33") (pin "5") (pinfunction "5_5") (pintype "passive"))
    )
    (net (code "66") (name "PACK+FUSED") (class "Default")
      (node (ref "R2") (pin "2") (pinfunction "2_2") (pintype "passive"))
      (node (ref "R27") (pin "1") (pinfunction "1_1") (pintype "passive"))
      (node (ref "TP13") (pin "1") (pinfunction "P$1_1") (pintype "passive"))
    )
    (net (code "67") (name "PRECHARGE_OK") (class "Default")
      (node (ref "J3") (pin "3") (pinfunction "3_3") (pintype "passive"))
      (node (ref "R29") (pin "2") (pinfunction "2_2") (pintype "passive"))
      (node (ref "TP4") (pin "1") (pinfunction "P$1_1") (pintype "passive"))
      (node (ref "U1") (pin "1") (pinfunction "IN_1") (pintype "bidirectional"))
      (node (ref "U15") (pin "2") (pinfunction "IN_2") (pintype "input"))
    )
    (net (code "68") (name "SHDN") (class "Default")
      (node (ref "D7") (pin "1") (pinfunction "C_1") (pintype "passive"))
      (node (ref "D8") (pin "1") (pinfunction "C_1") (pintype "passive"))
      (node (ref "J3") (pin "2") (pinfunction "2_2") (pintype "passive"))
      (node (ref "K4") (pin "2") (pinfunction "COIL+_2") (pintype "bidirectional"))
      (node (ref "K5") (pin "2") (pinfunction "COIL+_2") (pintype "bidirectional"))
      (node (ref "R36") (pin "2") (pinfunction "2_2") (pintype "passive"))
      (node (ref "R54") (pin "2") (pinfunction "2_2") (pintype "passive"))
      (node (ref "TP11") (pin "1") (pinfunction "P$1_1") (pintype "passive"))
    )
    (net (code "69") (name "TS+5V") (class "Default")
      (node (ref "C34") (pin "1") (pinfunction "1_1") (pintype "passive"))
      (node (ref "C36") (pin "1") (pinfunction "1_1") (pintype "passive"))
      (node (ref "C37") (pin "1") (pinfunction "1_1") (pintype "passive"))
      (node (ref "C39") (pin "1") (pinfunction "1_1") (pintype "passive"))
      (node (ref "C40") (pin "1") (pinfunction "1_1") (pintype "passive"))
      (node (ref "C46") (pin "1") (pinfunction "1_1") (pintype "passive"))
      (node (ref "C47") (pin "1") (pinfunction "1_1") (pintype "passive"))
      (node (ref "L6") (pin "2") (pinfunction "2_2") (pintype "passive"))
      (node (ref "R55") (pin "2") (pinfunction "2_2") (pintype "passive"))
      (node (ref "R63") (pin "1") (pinfunction "1_1") (pintype "passive"))
      (node (ref "TP20") (pin "1") (pinfunction "P$1_1") (pintype "passive"))
      (node (ref "U16") (pin "9") (pinfunction "VFB_9") (pintype "input"))
      (node (ref "U18") (pin "3") (pinfunction "VDD1_3") (pintype "power_in"))
      (node (ref "U19") (pin "3") (pinfunction "VDD1_3") (pintype "power_in"))
    )
    (net (code "70") (name "TS+FUSED") (class "Default")
      (node (ref "F6") (pin "2") (pinfunction "2_2") (pintype "passive"))
      (node (ref "L5") (pin "2") (pinfunction "2_2") (pintype "passive"))
      (node (ref "R1") (pin "2") (pinfunction "2_2") (pintype "passive"))
      (node (ref "R26") (pin "1") (pinfunction "1_1") (pintype "passive"))
      (node (ref "R31") (pin "2") (pinfunction "2_2") (pintype "passive"))
      (node (ref "U$33") (pin "4") (pinfunction "4_4") (pintype "passive"))
    )
    (net (code "71") (name "TS+UNFUSED") (class "Default")
      (node (ref "F6") (pin "1") (pinfunction "1_1") (pintype "passive"))
      (node (ref "K4") (pin "1") (pinfunction "CONTACT1_1") (pintype "bidirectional"))
      (node (ref "R39") (pin "2") (pinfunction "2_2") (pintype "passive"))
      (node (ref "R42") (pin "1") (pinfunction "1_1") (pintype "passive"))
      (node (ref "TP14") (pin "1") (pinfunction "P$1_1") (pintype "passive"))
      (node (ref "U$33") (pin "1") (pinfunction "1_1") (pintype "passive"))
      (node (ref "U$33") (pin "2") (pinfunction "2_2") (pintype "passive"))
    )
    (net (code "72") (name "TS-FUSED") (class "Default")
      (node (ref "C1") (pin "2") (pinfunction "2_2") (pintype "passive"))
      (node (ref "C2") (pin "2") (pinfunction "2_2") (pintype "passive"))
      (node (ref "C24") (pin "2") (pinfunction "2_2") (pintype "passive"))
      (node (ref "C25") (pin "2") (pinfunction "2_2") (pintype "passive"))
      (node (ref "C3") (pin "2") (pinfunction "2_2") (pintype "passive"))
      (node (ref "C30") (pin "2") (pinfunction "2_2") (pintype "passive"))
      (node (ref "C31") (pin "2") (pinfunction "2_2") (pintype "passive"))
      (node (ref "C32") (pin "2") (pinfunction "2_2") (pintype "passive"))
      (node (ref "C33") (pin "2") (pinfunction "2_2") (pintype "passive"))
      (node (ref "C34") (pin "2") (pinfunction "2_2") (pintype "passive"))
      (node (ref "C36") (pin "2") (pinfunction "2_2") (pintype "passive"))
      (node (ref "C37") (pin "2") (pinfunction "2_2") (pintype "passive"))
      (node (ref "C38") (pin "2") (pinfunction "2_2") (pintype "passive"))
      (node (ref "C39") (pin "2") (pinfunction "2_2") (pintype "passive"))
      (node (ref "C4") (pin "2") (pinfunction "2_2") (pintype "passive"))
      (node (ref "C40") (pin "2") (pinfunction "2_2") (pintype "passive"))
      (node (ref "C45") (pin "2") (pinfunction "2_2") (pintype "passive"))
      (node (ref "C46") (pin "2") (pinfunction "2_2") (pintype "passive"))
      (node (ref "C47") (pin "2") (pinfunction "2_2") (pintype "passive"))
      (node (ref "C48") (pin "2") (pinfunction "2_2") (pintype "passive"))
      (node (ref "C49") (pin "2") (pinfunction "2_2") (pintype "passive"))
      (node (ref "D13") (pin "1") (pinfunction "C_1") (pintype "passive"))
      (node (ref "D14") (pin "1") (pinfunction "C_1") (pintype "passive"))
      (node (ref "D6") (pin "1") (pinfunction "C_1") (pintype "passive"))
      (node (ref "F2") (pin "2") (pinfunction "2_2") (pintype "passive"))
      (node (ref "R14") (pin "1") (pinfunction "1_1") (pintype "passive"))
      (node (ref "R15") (pin "1") (pinfunction "1_1") (pintype "passive"))
      (node (ref "R24") (pin "1") (pinfunction "1_1") (pintype "passive"))
      (node (ref "R25") (pin "1") (pinfunction "1_1") (pintype "passive"))
      (node (ref "R3") (pin "1") (pinfunction "1_1") (pintype "passive"))
      (node (ref "R33") (pin "2") (pinfunction "2_2") (pintype "passive"))
      (node (ref "R39") (pin "3") (pinfunction "3_3") (pintype "passive"))
      (node (ref "R39") (pin "4") (pinfunction "3_4") (pintype "passive"))
      (node (ref "R39") (pin "5") (pinfunction "3_5") (pintype "passive"))
      (node (ref "R39") (pin "6") (pinfunction "3_6") (pintype "passive"))
      (node (ref "R40") (pin "3") (pinfunction "3_3") (pintype "passive"))
      (node (ref "R40") (pin "4") (pinfunction "3_4") (pintype "passive"))
      (node (ref "R40") (pin "5") (pinfunction "3_5") (pintype "passive"))
      (node (ref "R40") (pin "6") (pinfunction "3_6") (pintype "passive"))
      (node (ref "R41") (pin "3") (pinfunction "3_3") (pintype "passive"))
      (node (ref "R41") (pin "4") (pinfunction "3_4") (pintype "passive"))
      (node (ref "R41") (pin "5") (pinfunction "3_5") (pintype "passive"))
      (node (ref "R41") (pin "6") (pinfunction "3_6") (pintype "passive"))
      (node (ref "R42") (pin "3") (pinfunction "3_3") (pintype "passive"))
      (node (ref "R42") (pin "4") (pinfunction "3_4") (pintype "passive"))
      (node (ref "R42") (pin "5") (pinfunction "3_5") (pintype "passive"))
      (node (ref "R42") (pin "6") (pinfunction "3_6") (pintype "passive"))
      (node (ref "R45") (pin "1") (pinfunction "1_1") (pintype "passive"))
      (node (ref "R48") (pin "1") (pinfunction "1_1") (pintype "passive"))
      (node (ref "TP16") (pin "1") (pinfunction "P$1_1") (pintype "passive"))
      (node (ref "U$31") (pin "1") (pinfunction "1_1") (pintype "passive"))
      (node (ref "U$31") (pin "2") (pinfunction "2_2") (pintype "passive"))
      (node (ref "U10") (pin "5") (pinfunction "-IN_5") (pintype "power_in"))
      (node (ref "U11") (pin "3") (pinfunction "CONTACT1_3") (pintype "bidirectional"))
      (node (ref "U16") (pin "16") (pinfunction "GND_16") (pintype "power_in"))
      (node (ref "U16") (pin "6") (pinfunction "VPRG2_6") (pintype "input"))
      (node (ref "U16") (pin "8") (pinfunction "GND_8") (pintype "power_in"))
      (node (ref "U18") (pin "4") (pinfunction "GND1_4") (pintype "power_in"))
      (node (ref "U19") (pin "4") (pinfunction "GND1_4") (pintype "power_in"))
    )
    (net (code "73") (name "TS-UNFUSED") (class "Default")
      (node (ref "F2") (pin "1") (pinfunction "1_1") (pintype "passive"))
      (node (ref "R40") (pin "2") (pinfunction "2_2") (pintype "passive"))
      (node (ref "R41") (pin "1") (pinfunction "1_1") (pintype "passive"))
      (node (ref "TP15") (pin "1") (pinfunction "P$1_1") (pintype "passive"))
      (node (ref "U$31") (pin "5") (pinfunction "5_5") (pintype "passive"))
    )
    (net (code "74") (name "TSMP+") (class "Default")
      (node (ref "R42") (pin "2") (pinfunction "2_2") (pintype "passive"))
      (node (ref "TP18") (pin "1") (pinfunction "P$1_1") (pintype "passive"))
      (node (ref "U$33") (pin "3") (pinfunction "3_3") (pintype "passive"))
    )
    (net (code "75") (name "TSMP-") (class "Default")
      (node (ref "R41") (pin "2") (pinfunction "2_2") (pintype "passive"))
      (node (ref "TP19") (pin "1") (pinfunction "P$1_1") (pintype "passive"))
      (node (ref "U$31") (pin "4") (pinfunction "4_4") (pintype "passive"))
    )
    (net (code "76") (name "VDD") (class "Default")
      (node (ref "C41") (pin "1") (pinfunction "1_1") (pintype "passive"))
      (node (ref "C42") (pin "1") (pinfunction "1_1") (pintype "passive"))
      (node (ref "C43") (pin "1") (pinfunction "1_1") (pintype "passive"))
      (node (ref "C44") (pin "1") (pinfunction "1_1") (pintype "passive"))
      (node (ref "C5") (pin "1") (pinfunction "1_1") (pintype "passive"))
      (node (ref "C7") (pin "1") (pinfunction "1_1") (pintype "passive"))
      (node (ref "C9") (pin "1") (pinfunction "1_1") (pintype "passive"))
      (node (ref "R44") (pin "2") (pinfunction "2_2") (pintype "passive"))
      (node (ref "R53") (pin "1") (pinfunction "1_1") (pintype "passive"))
      (node (ref "TP2") (pin "1") (pinfunction "P$1_1") (pintype "passive"))
      (node (ref "U1") (pin "5") (pinfunction "V+_5") (pintype "power_in"))
      (node (ref "U15") (pin "5") (pinfunction "VDD_5") (pintype "power_in"))
      (node (ref "U18") (pin "8") (pinfunction "VDD2_8") (pintype "power_in"))
      (node (ref "U19") (pin "8") (pinfunction "VDD2_8") (pintype "power_in"))
      (node (ref "U2") (pin "2") (pinfunction "OUT_2") (pintype "power_in"))
      (node (ref "U2") (pin "4") (pinfunction "OUT_4") (pintype "power_in"))
    )
    (net (code "77") (name "unconnected-(U16-FBO-Pad5)") (class "Default")
      (node (ref "U16") (pin "5") (pinfunction "FBO_5") (pintype "output"))
    )
  )
)
